# Mfd3.net
KiCad netlist of a schematic drawn in Altium Designer
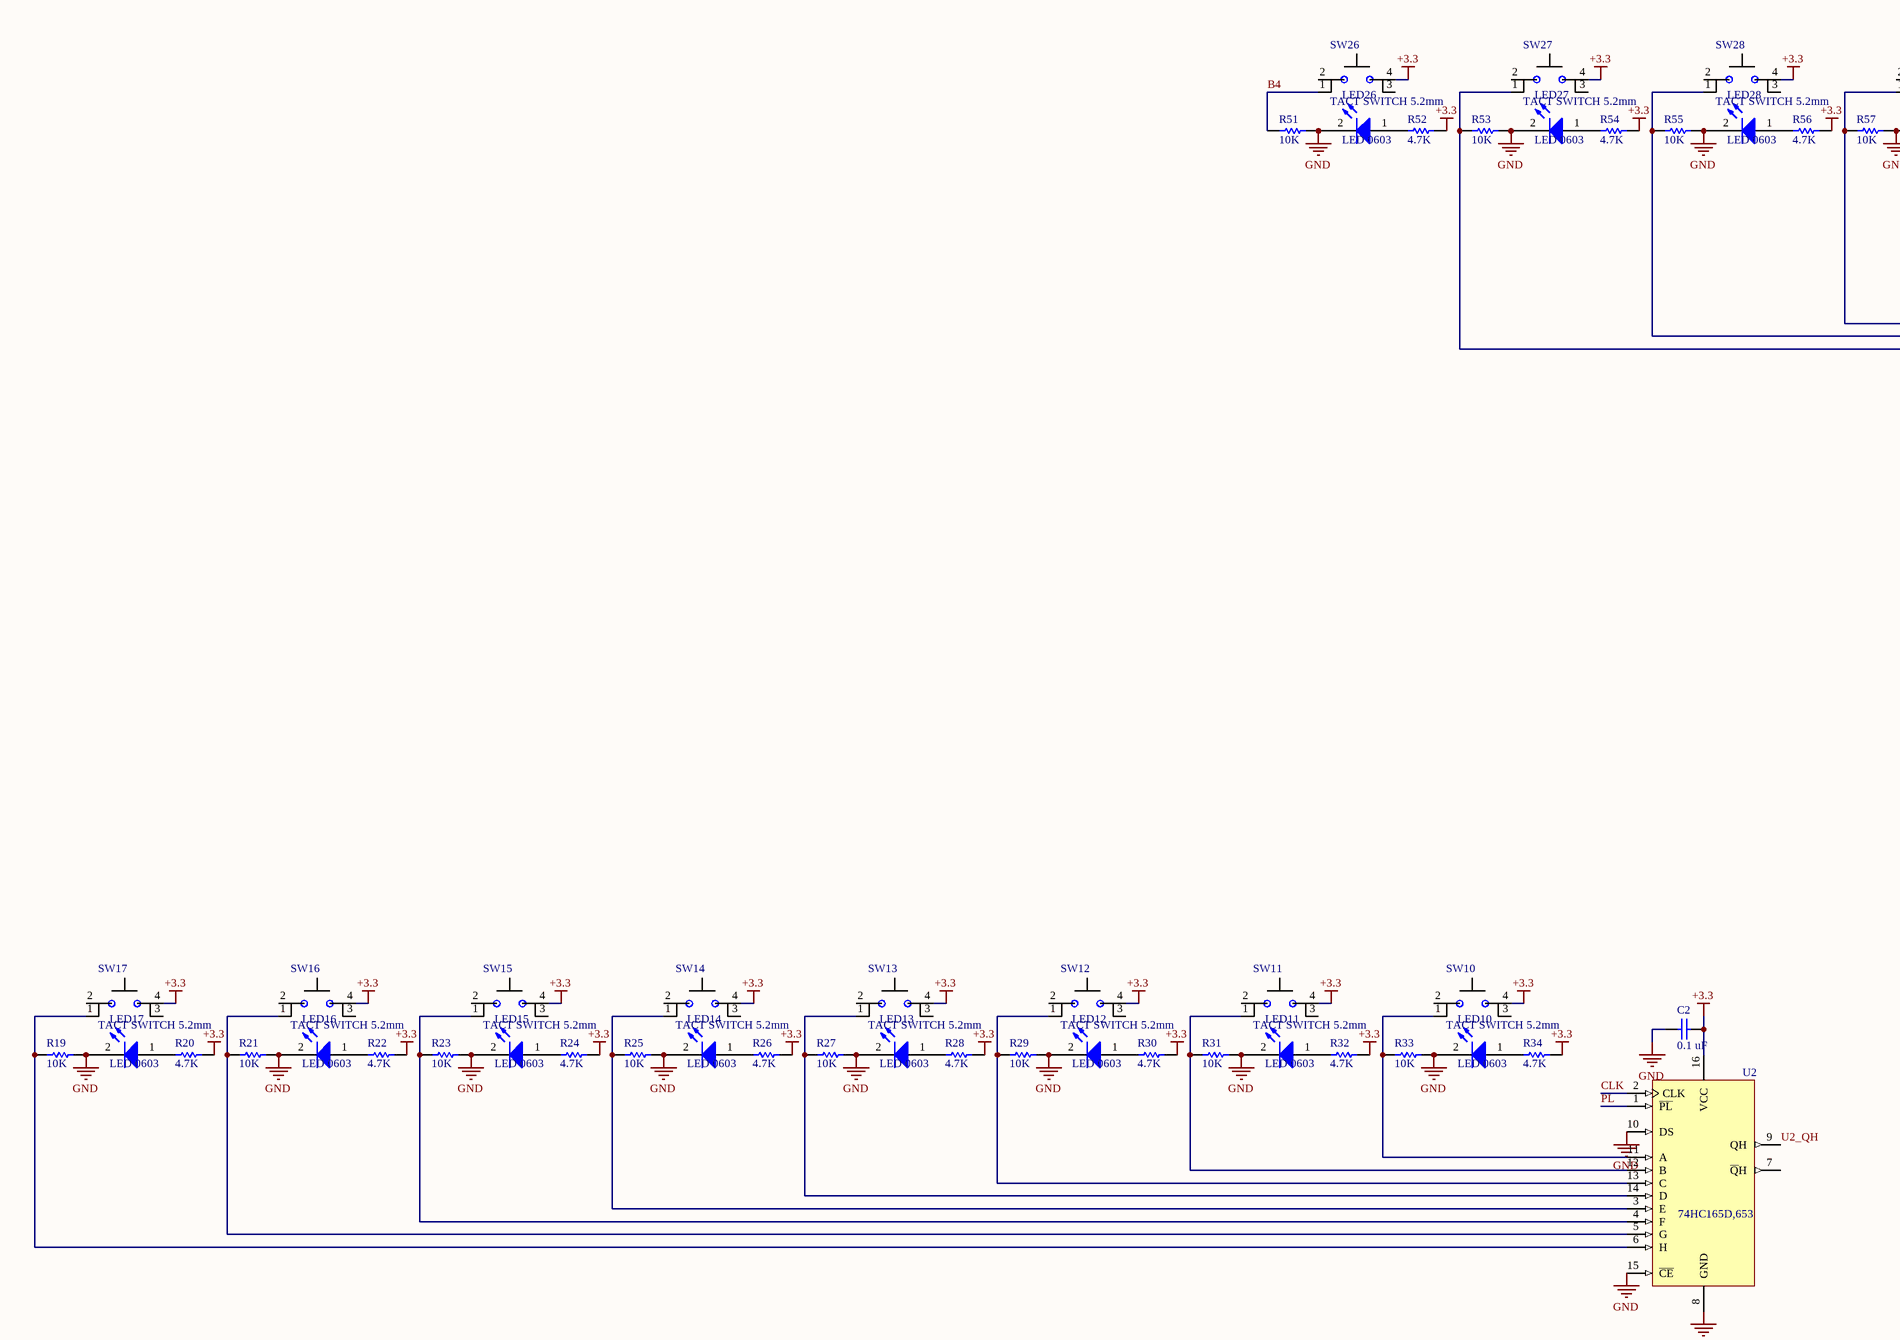
[diagram p0: Mfd3.SchDoc, top left]
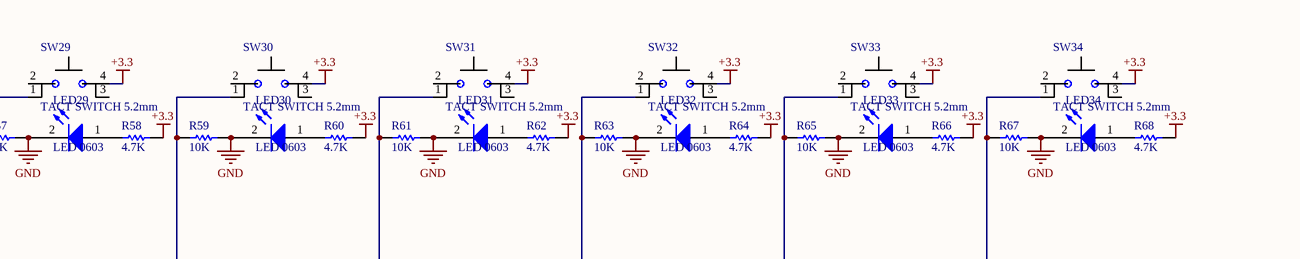
[diagram p1: Mfd3.SchDoc, top middle]
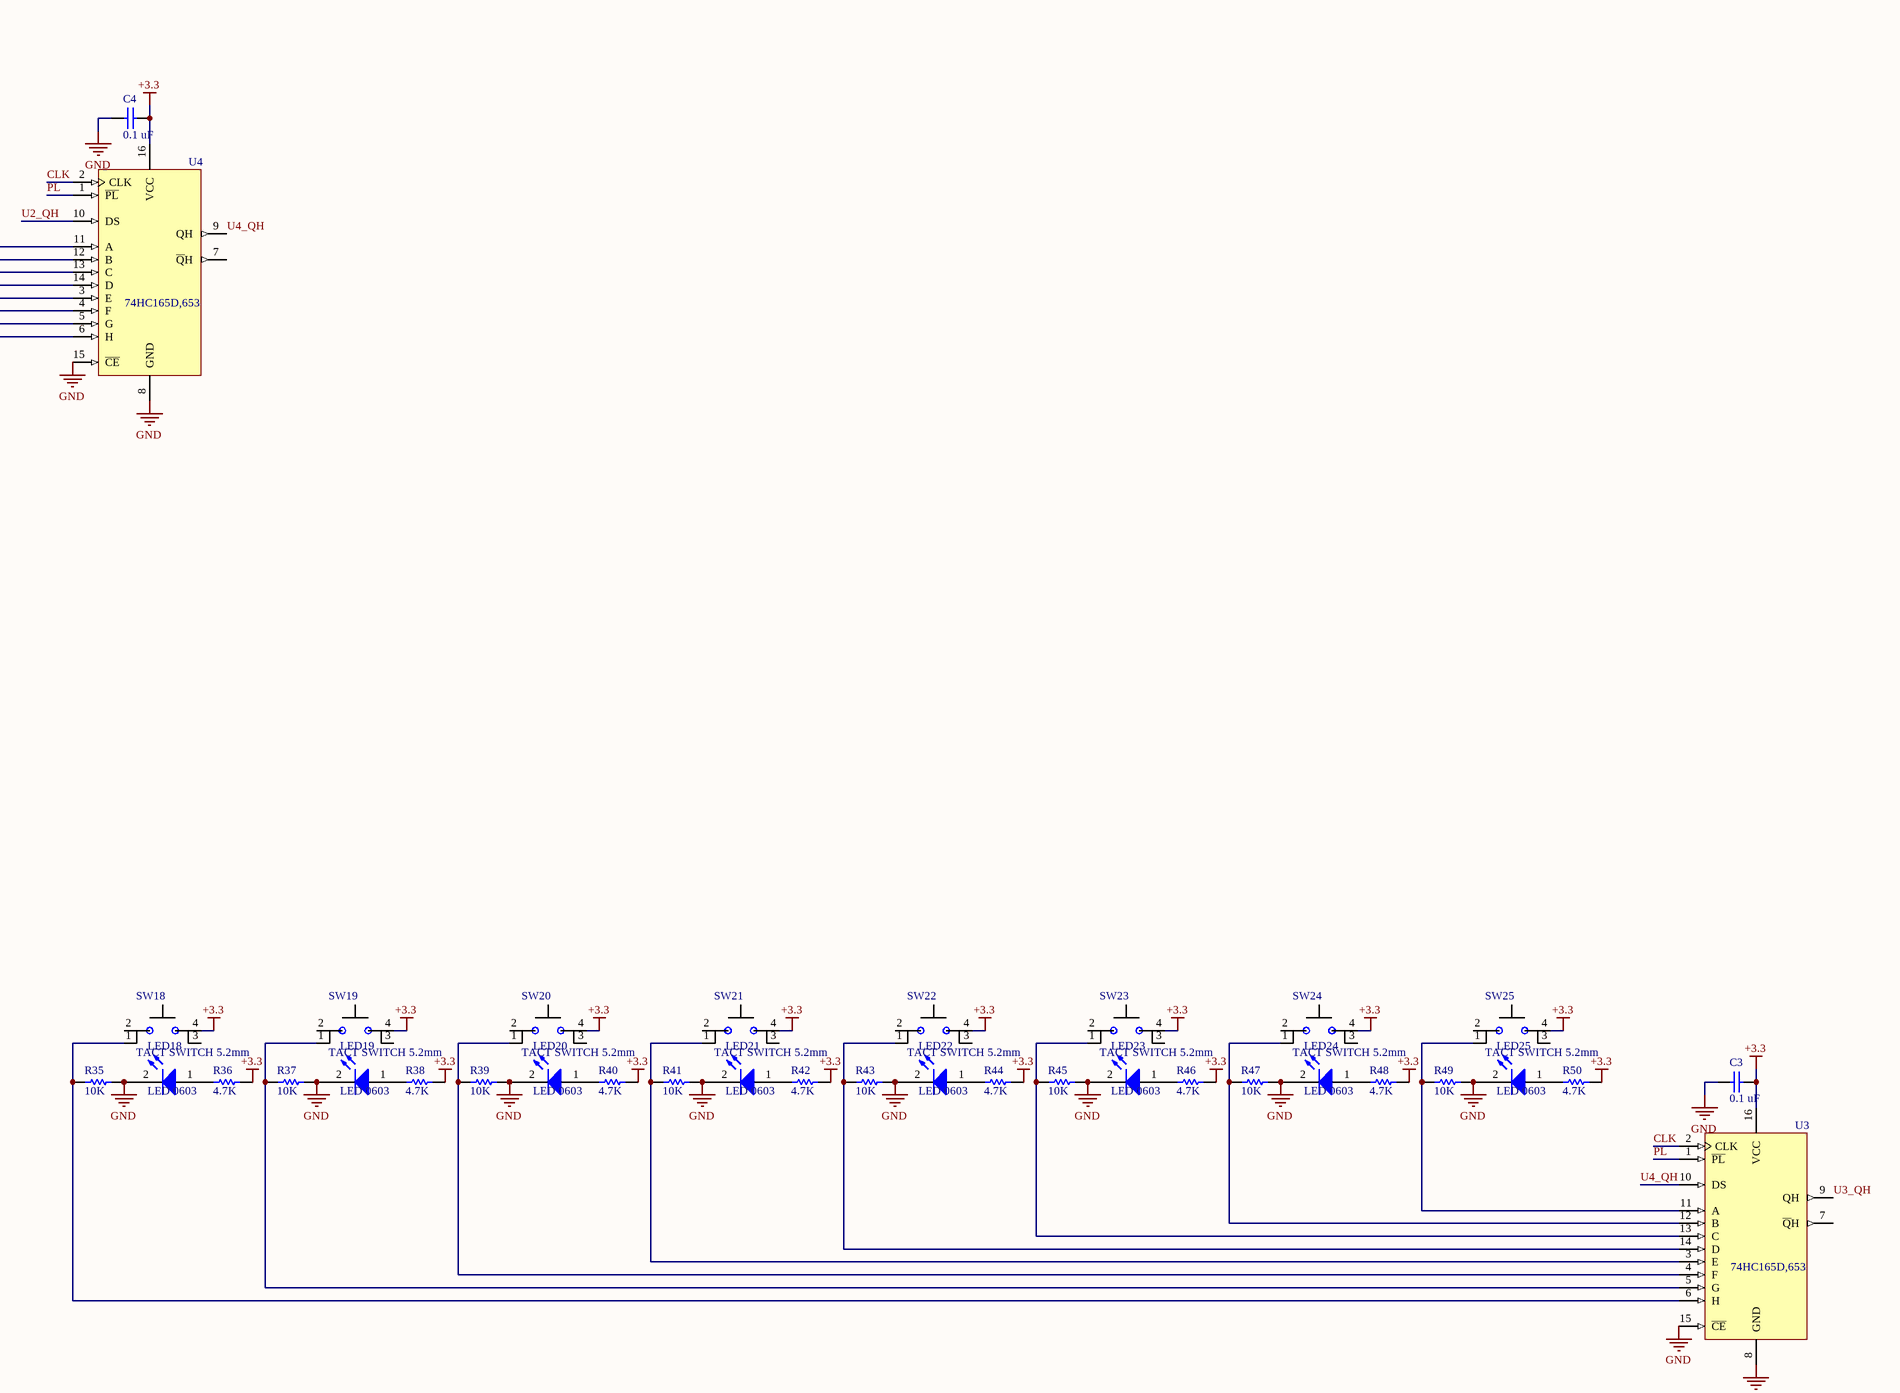
[diagram p2: Mfd3.SchDoc, top right]
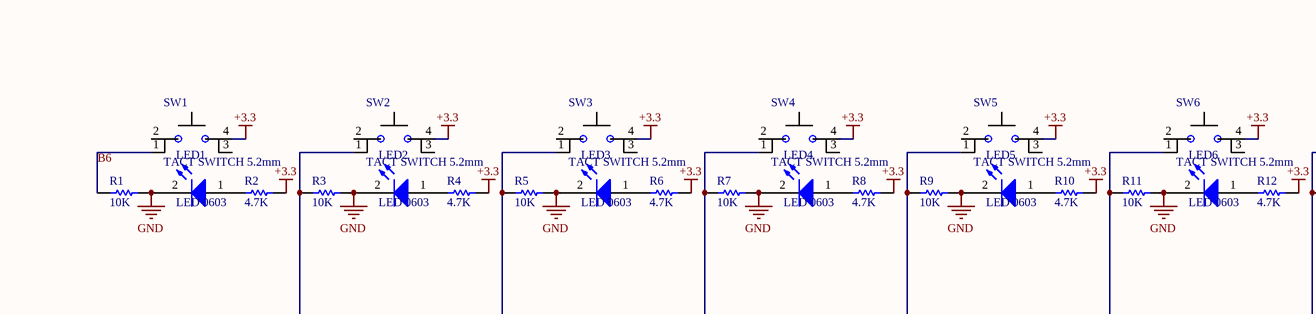
[diagram p3: Mfd3.SchDoc, bottom left]
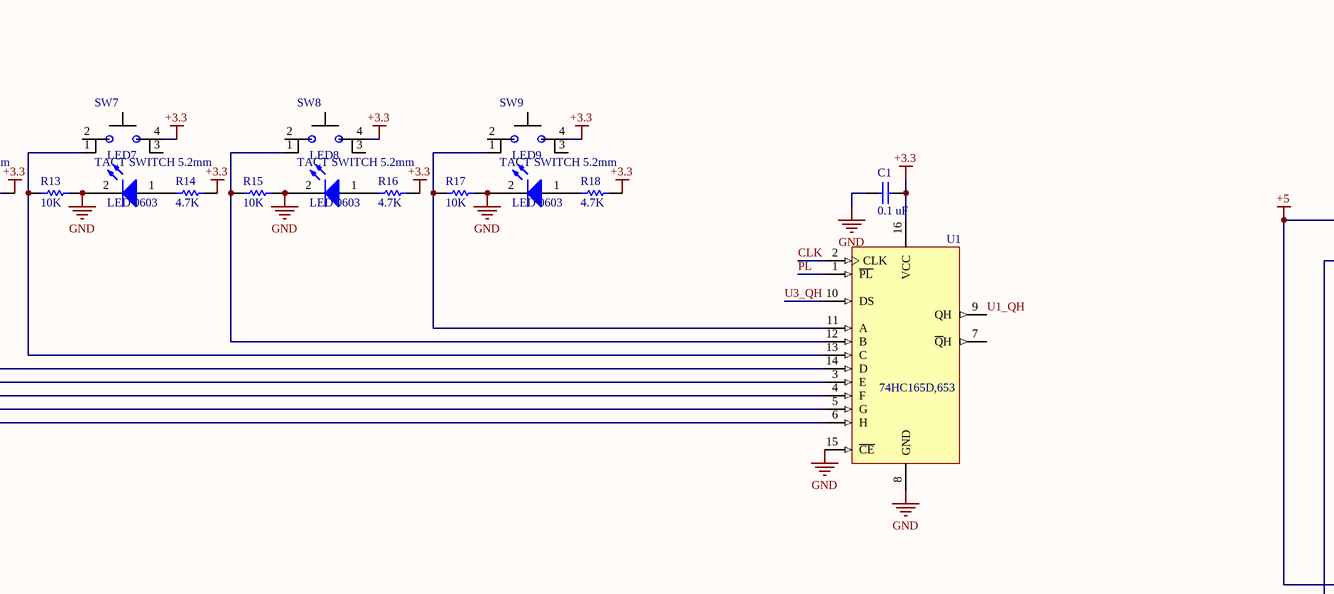
[diagram p4: Mfd3.SchDoc, bottom middle]
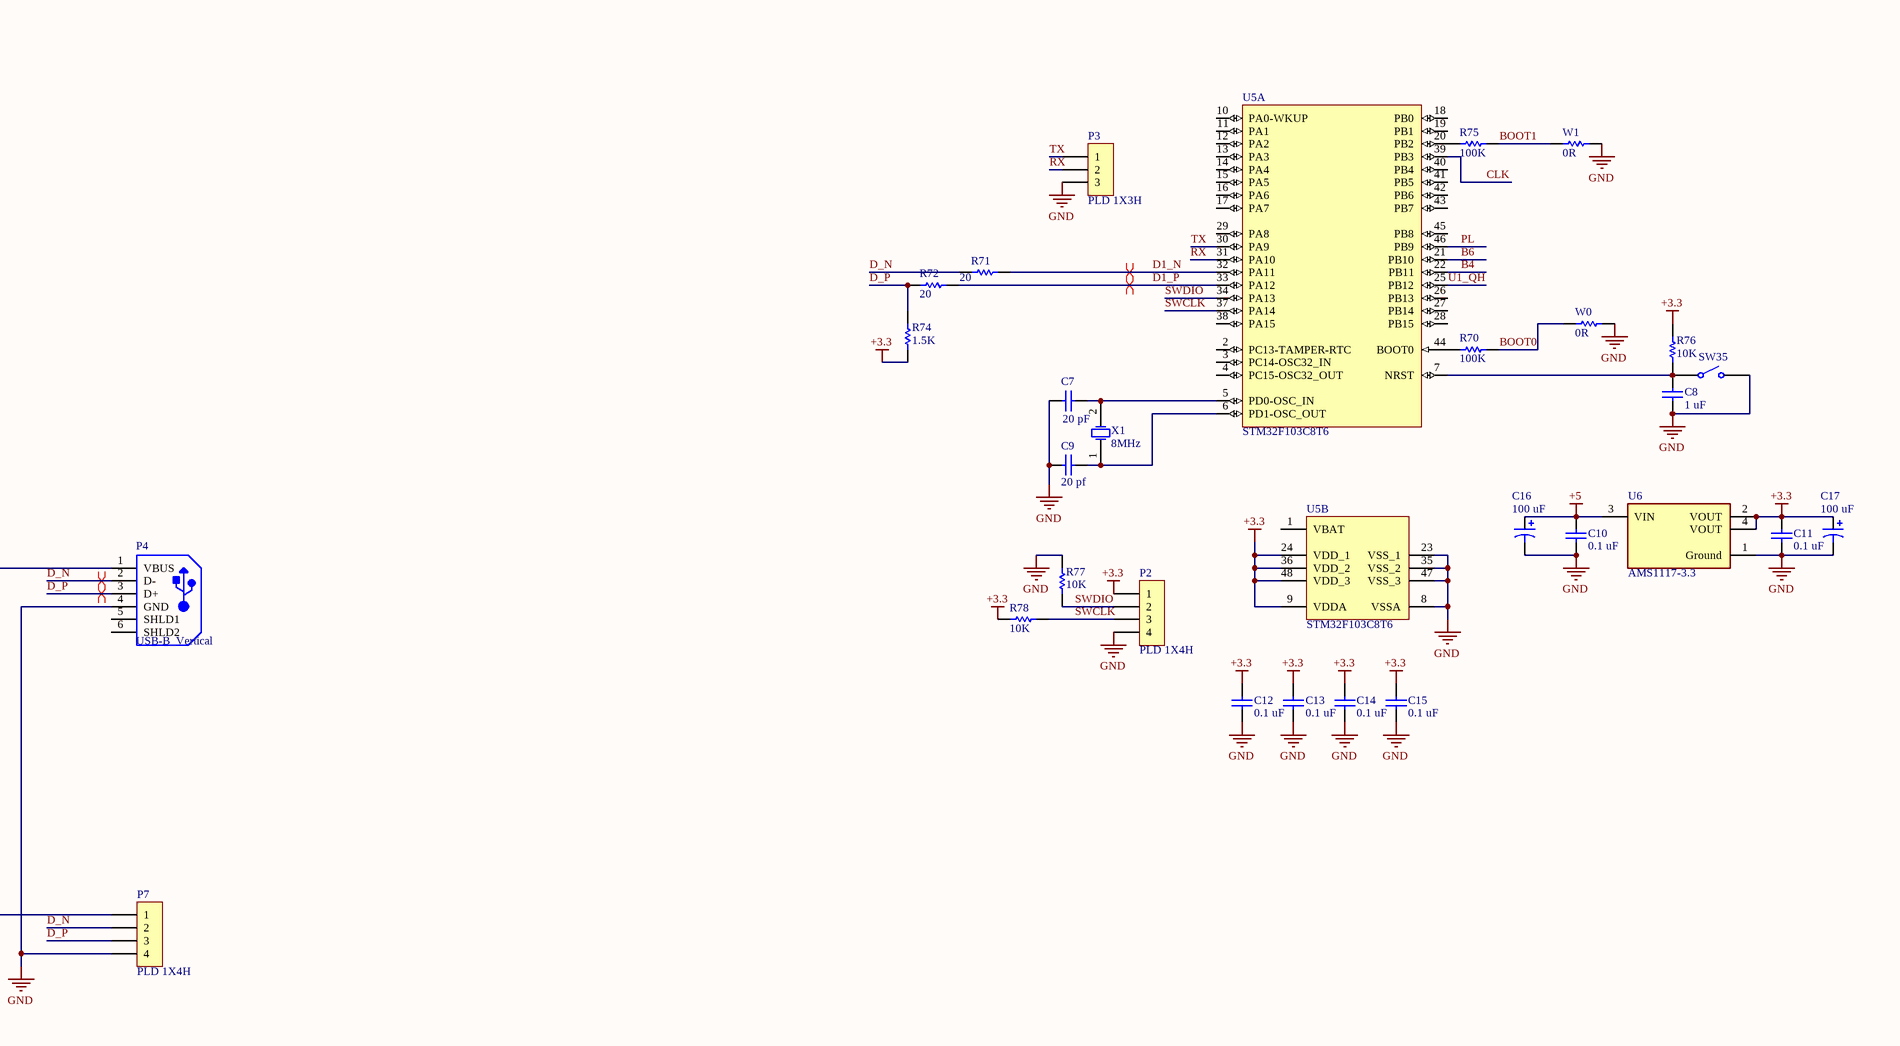
[diagram p5: Mfd3.SchDoc, bottom right]

(export (version "E")
  (design (tool "Eeschema 10.0.6"))
  (components
    (comp (ref "C1")
      (value "0.1 uF")
      (footprint "1206-CAP")
      (description "Chip Capacitor, 1206")
      (fields (field (name "LCSC PART #") "C24497"))
      (libsource (lib "Mfd3Schlib") (part "Capacitor"))
    )
    (comp (ref "C2")
      (value "0.1 uF")
      (footprint "1206-CAP")
      (description "Chip Capacitor, 1206")
      (fields (field (name "LCSC PART #") "C24497"))
      (libsource (lib "Mfd3Schlib") (part "Capacitor"))
    )
    (comp (ref "C3")
      (value "0.1 uF")
      (footprint "1206-CAP")
      (description "Chip Capacitor, 1206")
      (fields (field (name "LCSC PART #") "C24497"))
      (libsource (lib "Mfd3Schlib") (part "Capacitor"))
    )
    (comp (ref "C4")
      (value "0.1 uF")
      (footprint "1206-CAP")
      (description "Chip Capacitor, 1206")
      (fields (field (name "LCSC PART #") "C24497"))
      (libsource (lib "Mfd3Schlib") (part "Capacitor"))
    )
    (comp (ref "C7")
      (value "20 pF")
      (footprint "0805 CAP")
      (description "Chip Capacitor, 1206")
      (fields (field (name "LCSC PART #") "C1798"))
      (libsource (lib "Mfd3Schlib") (part "Capacitor"))
    )
    (comp (ref "C8")
      (value "1 uF")
      (footprint "1206-CAP")
      (description "Chip Capacitor, 1206")
      (fields (field (name "LCSC PART #") "C1848"))
      (libsource (lib "Mfd3Schlib") (part "Capacitor"))
    )
    (comp (ref "C9")
      (value "20 pf")
      (footprint "0805 CAP")
      (description "Chip Capacitor, 1206")
      (fields (field (name "LCSC PART #") "C1798"))
      (libsource (lib "Mfd3Schlib") (part "Capacitor"))
    )
    (comp (ref "C10")
      (value "0.1 uF")
      (footprint "1206-CAP")
      (description "Chip Capacitor, 1206")
      (fields (field (name "LCSC PART #") "C24497"))
      (libsource (lib "Mfd3Schlib") (part "Capacitor"))
    )
    (comp (ref "C11")
      (value "0.1 uF")
      (footprint "1206-CAP")
      (description "Chip Capacitor, 1206")
      (fields (field (name "LCSC PART #") "C24497"))
      (libsource (lib "Mfd3Schlib") (part "Capacitor"))
    )
    (comp (ref "C12")
      (value "0.1 uF")
      (footprint "1206-CAP")
      (description "Chip Capacitor, 1206")
      (fields (field (name "LCSC PART #") "C24497"))
      (libsource (lib "Mfd3Schlib") (part "Capacitor"))
    )
    (comp (ref "C13")
      (value "0.1 uF")
      (footprint "1206-CAP")
      (description "Chip Capacitor, 1206")
      (fields (field (name "LCSC PART #") "C24497"))
      (libsource (lib "Mfd3Schlib") (part "Capacitor"))
    )
    (comp (ref "C14")
      (value "0.1 uF")
      (footprint "1206-CAP")
      (description "Chip Capacitor, 1206")
      (fields (field (name "LCSC PART #") "C24497"))
      (libsource (lib "Mfd3Schlib") (part "Capacitor"))
    )
    (comp (ref "C15")
      (value "0.1 uF")
      (footprint "1206-CAP")
      (description "Chip Capacitor, 1206")
      (fields (field (name "LCSC PART #") "C24497"))
      (libsource (lib "Mfd3Schlib") (part "Capacitor"))
    )
    (comp (ref "C16")
      (value "100 uF")
      (footprint "1210 Cap")
      (description "Tantalum Capacitor, 1210")
      (fields (field (name "LCSC PART #") "C16133"))
      (libsource (lib "Mfd3Schlib") (part "Capacitor Tantalum"))
    )
    (comp (ref "C17")
      (value "100 uF")
      (footprint "1210 Cap")
      (description "Tantalum Capacitor, 1210")
      (fields (field (name "LCSC PART #") "C16133"))
      (libsource (lib "Mfd3Schlib") (part "Capacitor Tantalum"))
    )
    (comp (ref "LED1")
      (value "LED 0603")
      (footprint "LED 0603")
      (fields (field (name "LCSC PART #") "C72043"))
      (libsource (lib "Mfd3Schlib") (part "LED 0603"))
    )
    (comp (ref "LED2")
      (value "LED 0603")
      (footprint "LED 0603")
      (fields (field (name "LCSC PART #") "C72043"))
      (libsource (lib "Mfd3Schlib") (part "LED 0603"))
    )
    (comp (ref "LED3")
      (value "LED 0603")
      (footprint "LED 0603")
      (fields (field (name "LCSC PART #") "C72043"))
      (libsource (lib "Mfd3Schlib") (part "LED 0603"))
    )
    (comp (ref "LED4")
      (value "LED 0603")
      (footprint "LED 0603")
      (fields (field (name "LCSC PART #") "C72043"))
      (libsource (lib "Mfd3Schlib") (part "LED 0603"))
    )
    (comp (ref "LED5")
      (value "LED 0603")
      (footprint "LED 0603")
      (fields (field (name "LCSC PART #") "C72043"))
      (libsource (lib "Mfd3Schlib") (part "LED 0603"))
    )
    (comp (ref "LED6")
      (value "LED 0603")
      (footprint "LED 0603")
      (fields (field (name "LCSC PART #") "C72043"))
      (libsource (lib "Mfd3Schlib") (part "LED 0603"))
    )
    (comp (ref "LED7")
      (value "LED 0603")
      (footprint "LED 0603")
      (fields (field (name "LCSC PART #") "C72043"))
      (libsource (lib "Mfd3Schlib") (part "LED 0603"))
    )
    (comp (ref "LED8")
      (value "LED 0603")
      (footprint "LED 0603")
      (fields (field (name "LCSC PART #") "C72043"))
      (libsource (lib "Mfd3Schlib") (part "LED 0603"))
    )
    (comp (ref "LED9")
      (value "LED 0603")
      (footprint "LED 0603")
      (fields (field (name "LCSC PART #") "C72043"))
      (libsource (lib "Mfd3Schlib") (part "LED 0603"))
    )
    (comp (ref "LED10")
      (value "LED 0603")
      (footprint "LED 0603")
      (fields (field (name "LCSC PART #") "C72043"))
      (libsource (lib "Mfd3Schlib") (part "LED 0603"))
    )
    (comp (ref "LED11")
      (value "LED 0603")
      (footprint "LED 0603")
      (fields (field (name "LCSC PART #") "C72043"))
      (libsource (lib "Mfd3Schlib") (part "LED 0603"))
    )
    (comp (ref "LED12")
      (value "LED 0603")
      (footprint "LED 0603")
      (fields (field (name "LCSC PART #") "C72043"))
      (libsource (lib "Mfd3Schlib") (part "LED 0603"))
    )
    (comp (ref "LED13")
      (value "LED 0603")
      (footprint "LED 0603")
      (fields (field (name "LCSC PART #") "C72043"))
      (libsource (lib "Mfd3Schlib") (part "LED 0603"))
    )
    (comp (ref "LED14")
      (value "LED 0603")
      (footprint "LED 0603")
      (fields (field (name "LCSC PART #") "C72043"))
      (libsource (lib "Mfd3Schlib") (part "LED 0603"))
    )
    (comp (ref "LED15")
      (value "LED 0603")
      (footprint "LED 0603")
      (fields (field (name "LCSC PART #") "C72043"))
      (libsource (lib "Mfd3Schlib") (part "LED 0603"))
    )
    (comp (ref "LED16")
      (value "LED 0603")
      (footprint "LED 0603")
      (fields (field (name "LCSC PART #") "C72043"))
      (libsource (lib "Mfd3Schlib") (part "LED 0603"))
    )
    (comp (ref "LED17")
      (value "LED 0603")
      (footprint "LED 0603")
      (fields (field (name "LCSC PART #") "C72043"))
      (libsource (lib "Mfd3Schlib") (part "LED 0603"))
    )
    (comp (ref "LED18")
      (value "LED 0603")
      (footprint "LED 0603")
      (fields (field (name "LCSC PART #") "C72043"))
      (libsource (lib "Mfd3Schlib") (part "LED 0603"))
    )
    (comp (ref "LED19")
      (value "LED 0603")
      (footprint "LED 0603")
      (fields (field (name "LCSC PART #") "C72043"))
      (libsource (lib "Mfd3Schlib") (part "LED 0603"))
    )
    (comp (ref "LED20")
      (value "LED 0603")
      (footprint "LED 0603")
      (fields (field (name "LCSC PART #") "C72043"))
      (libsource (lib "Mfd3Schlib") (part "LED 0603"))
    )
    (comp (ref "LED21")
      (value "LED 0603")
      (footprint "LED 0603")
      (fields (field (name "LCSC PART #") "C72043"))
      (libsource (lib "Mfd3Schlib") (part "LED 0603"))
    )
    (comp (ref "LED22")
      (value "LED 0603")
      (footprint "LED 0603")
      (fields (field (name "LCSC PART #") "C72043"))
      (libsource (lib "Mfd3Schlib") (part "LED 0603"))
    )
    (comp (ref "LED23")
      (value "LED 0603")
      (footprint "LED 0603")
      (fields (field (name "LCSC PART #") "C72043"))
      (libsource (lib "Mfd3Schlib") (part "LED 0603"))
    )
    (comp (ref "LED24")
      (value "LED 0603")
      (footprint "LED 0603")
      (fields (field (name "LCSC PART #") "C72043"))
      (libsource (lib "Mfd3Schlib") (part "LED 0603"))
    )
    (comp (ref "LED25")
      (value "LED 0603")
      (footprint "LED 0603")
      (fields (field (name "LCSC PART #") "C72043"))
      (libsource (lib "Mfd3Schlib") (part "LED 0603"))
    )
    (comp (ref "LED26")
      (value "LED 0603")
      (footprint "LED 0603")
      (fields (field (name "LCSC PART #") "C72043"))
      (libsource (lib "Mfd3Schlib") (part "LED 0603"))
    )
    (comp (ref "LED27")
      (value "LED 0603")
      (footprint "LED 0603")
      (fields (field (name "LCSC PART #") "C72043"))
      (libsource (lib "Mfd3Schlib") (part "LED 0603"))
    )
    (comp (ref "LED28")
      (value "LED 0603")
      (footprint "LED 0603")
      (fields (field (name "LCSC PART #") "C72043"))
      (libsource (lib "Mfd3Schlib") (part "LED 0603"))
    )
    (comp (ref "LED29")
      (value "LED 0603")
      (footprint "LED 0603")
      (fields (field (name "LCSC PART #") "C72043"))
      (libsource (lib "Mfd3Schlib") (part "LED 0603"))
    )
    (comp (ref "LED30")
      (value "LED 0603")
      (footprint "LED 0603")
      (fields (field (name "LCSC PART #") "C72043"))
      (libsource (lib "Mfd3Schlib") (part "LED 0603"))
    )
    (comp (ref "LED31")
      (value "LED 0603")
      (footprint "LED 0603")
      (fields (field (name "LCSC PART #") "C72043"))
      (libsource (lib "Mfd3Schlib") (part "LED 0603"))
    )
    (comp (ref "LED32")
      (value "LED 0603")
      (footprint "LED 0603")
      (fields (field (name "LCSC PART #") "C72043"))
      (libsource (lib "Mfd3Schlib") (part "LED 0603"))
    )
    (comp (ref "LED33")
      (value "LED 0603")
      (footprint "LED 0603")
      (fields (field (name "LCSC PART #") "C72043"))
      (libsource (lib "Mfd3Schlib") (part "LED 0603"))
    )
    (comp (ref "LED34")
      (value "LED 0603")
      (footprint "LED 0603")
      (fields (field (name "LCSC PART #") "C72043"))
      (libsource (lib "Mfd3Schlib") (part "LED 0603"))
    )
    (comp (ref "P2")
      (value "PLD 1X4H")
      (footprint "PLD 1X4H")
      (description "Header, 4-Pin, SIngle row, Right Angle")
      (libsource (lib "MfdSchlib") (part "PLD 1X4H"))
    )
    (comp (ref "P3")
      (value "PLD 1X3H")
      (footprint "PLD 1X3H")
      (description "Header, 3-Pin, SIngle row, Right Angle")
      (libsource (lib "Mfd3Schlib") (part "PLD 1X3H"))
    )
    (comp (ref "P4")
      (value "USB-B_Vertical")
      (footprint "USB-B_Vertical")
      (libsource (lib "MfdSchlib") (part "USB-B_Vertical"))
    )
    (comp (ref "P7")
      (value "PLD 1X4H")
      (footprint "PLD 1X4H")
      (description "Header, 4-Pin, SIngle row, Right Angle")
      (libsource (lib "MfdSchlib") (part "PLD 1X4H"))
    )
    (comp (ref "R1")
      (value "10K")
      (footprint "1206")
      (description "Resistor 1206")
      (fields (field (name "LCSC PART #") "C17902"))
      (libsource (lib "MfdSchlib") (part "Resistor"))
    )
    (comp (ref "R2")
      (value "4.7K")
      (footprint "1206")
      (description "Resistor 1206")
      (fields (field (name "LCSC PART #") "C17936"))
      (libsource (lib "MfdSchlib") (part "Resistor"))
    )
    (comp (ref "R3")
      (value "10K")
      (footprint "1206")
      (description "Resistor 1206")
      (fields (field (name "LCSC PART #") "C17902"))
      (libsource (lib "MfdSchlib") (part "Resistor"))
    )
    (comp (ref "R4")
      (value "4.7K")
      (footprint "1206")
      (description "Resistor 1206")
      (fields (field (name "LCSC PART #") "C17936"))
      (libsource (lib "MfdSchlib") (part "Resistor"))
    )
    (comp (ref "R5")
      (value "10K")
      (footprint "1206")
      (description "Resistor 1206")
      (fields (field (name "LCSC PART #") "C17902"))
      (libsource (lib "MfdSchlib") (part "Resistor"))
    )
    (comp (ref "R6")
      (value "4.7K")
      (footprint "1206")
      (description "Resistor 1206")
      (fields (field (name "LCSC PART #") "C17936"))
      (libsource (lib "MfdSchlib") (part "Resistor"))
    )
    (comp (ref "R7")
      (value "10K")
      (footprint "1206")
      (description "Resistor 1206")
      (fields (field (name "LCSC PART #") "C17902"))
      (libsource (lib "MfdSchlib") (part "Resistor"))
    )
    (comp (ref "R8")
      (value "4.7K")
      (footprint "1206")
      (description "Resistor 1206")
      (fields (field (name "LCSC PART #") "C17936"))
      (libsource (lib "MfdSchlib") (part "Resistor"))
    )
    (comp (ref "R9")
      (value "10K")
      (footprint "1206")
      (description "Resistor 1206")
      (fields (field (name "LCSC PART #") "C17902"))
      (libsource (lib "MfdSchlib") (part "Resistor"))
    )
    (comp (ref "R10")
      (value "4.7K")
      (footprint "1206")
      (description "Resistor 1206")
      (fields (field (name "LCSC PART #") "C17936"))
      (libsource (lib "MfdSchlib") (part "Resistor"))
    )
    (comp (ref "R11")
      (value "10K")
      (footprint "1206")
      (description "Resistor 1206")
      (fields (field (name "LCSC PART #") "C17902"))
      (libsource (lib "MfdSchlib") (part "Resistor"))
    )
    (comp (ref "R12")
      (value "4.7K")
      (footprint "1206")
      (description "Resistor 1206")
      (fields (field (name "LCSC PART #") "C17936"))
      (libsource (lib "MfdSchlib") (part "Resistor"))
    )
    (comp (ref "R13")
      (value "10K")
      (footprint "1206")
      (description "Resistor 1206")
      (fields (field (name "LCSC PART #") "C17902"))
      (libsource (lib "MfdSchlib") (part "Resistor"))
    )
    (comp (ref "R14")
      (value "4.7K")
      (footprint "1206")
      (description "Resistor 1206")
      (fields (field (name "LCSC PART #") "C17936"))
      (libsource (lib "MfdSchlib") (part "Resistor"))
    )
    (comp (ref "R15")
      (value "10K")
      (footprint "1206")
      (description "Resistor 1206")
      (fields (field (name "LCSC PART #") "C17902"))
      (libsource (lib "MfdSchlib") (part "Resistor"))
    )
    (comp (ref "R16")
      (value "4.7K")
      (footprint "1206")
      (description "Resistor 1206")
      (fields (field (name "LCSC PART #") "C17936"))
      (libsource (lib "MfdSchlib") (part "Resistor"))
    )
    (comp (ref "R17")
      (value "10K")
      (footprint "1206")
      (description "Resistor 1206")
      (fields (field (name "LCSC PART #") "C17902"))
      (libsource (lib "MfdSchlib") (part "Resistor"))
    )
    (comp (ref "R18")
      (value "4.7K")
      (footprint "1206")
      (description "Resistor 1206")
      (fields (field (name "LCSC PART #") "C17936"))
      (libsource (lib "MfdSchlib") (part "Resistor"))
    )
    (comp (ref "R19")
      (value "10K")
      (footprint "1206")
      (description "Resistor 1206")
      (fields (field (name "LCSC PART #") "C17902"))
      (libsource (lib "MfdSchlib") (part "Resistor"))
    )
    (comp (ref "R20")
      (value "4.7K")
      (footprint "1206")
      (description "Resistor 1206")
      (fields (field (name "LCSC PART #") "C17936"))
      (libsource (lib "MfdSchlib") (part "Resistor"))
    )
    (comp (ref "R21")
      (value "10K")
      (footprint "1206")
      (description "Resistor 1206")
      (fields (field (name "LCSC PART #") "C17902"))
      (libsource (lib "MfdSchlib") (part "Resistor"))
    )
    (comp (ref "R22")
      (value "4.7K")
      (footprint "1206")
      (description "Resistor 1206")
      (fields (field (name "LCSC PART #") "C17936"))
      (libsource (lib "MfdSchlib") (part "Resistor"))
    )
    (comp (ref "R23")
      (value "10K")
      (footprint "1206")
      (description "Resistor 1206")
      (fields (field (name "LCSC PART #") "C17902"))
      (libsource (lib "MfdSchlib") (part "Resistor"))
    )
    (comp (ref "R24")
      (value "4.7K")
      (footprint "1206")
      (description "Resistor 1206")
      (fields (field (name "LCSC PART #") "C17936"))
      (libsource (lib "MfdSchlib") (part "Resistor"))
    )
    (comp (ref "R25")
      (value "10K")
      (footprint "1206")
      (description "Resistor 1206")
      (fields (field (name "LCSC PART #") "C17902"))
      (libsource (lib "MfdSchlib") (part "Resistor"))
    )
    (comp (ref "R26")
      (value "4.7K")
      (footprint "1206")
      (description "Resistor 1206")
      (fields (field (name "LCSC PART #") "C17936"))
      (libsource (lib "MfdSchlib") (part "Resistor"))
    )
    (comp (ref "R27")
      (value "10K")
      (footprint "1206")
      (description "Resistor 1206")
      (fields (field (name "LCSC PART #") "C17902"))
      (libsource (lib "MfdSchlib") (part "Resistor"))
    )
    (comp (ref "R28")
      (value "4.7K")
      (footprint "1206")
      (description "Resistor 1206")
      (fields (field (name "LCSC PART #") "C17936"))
      (libsource (lib "MfdSchlib") (part "Resistor"))
    )
    (comp (ref "R29")
      (value "10K")
      (footprint "1206")
      (description "Resistor 1206")
      (fields (field (name "LCSC PART #") "C17902"))
      (libsource (lib "MfdSchlib") (part "Resistor"))
    )
    (comp (ref "R30")
      (value "4.7K")
      (footprint "1206")
      (description "Resistor 1206")
      (fields (field (name "LCSC PART #") "C17936"))
      (libsource (lib "MfdSchlib") (part "Resistor"))
    )
    (comp (ref "R31")
      (value "10K")
      (footprint "1206")
      (description "Resistor 1206")
      (fields (field (name "LCSC PART #") "C17902"))
      (libsource (lib "MfdSchlib") (part "Resistor"))
    )
    (comp (ref "R32")
      (value "4.7K")
      (footprint "1206")
      (description "Resistor 1206")
      (fields (field (name "LCSC PART #") "C17936"))
      (libsource (lib "MfdSchlib") (part "Resistor"))
    )
    (comp (ref "R33")
      (value "10K")
      (footprint "1206")
      (description "Resistor 1206")
      (fields (field (name "LCSC PART #") "C17902"))
      (libsource (lib "MfdSchlib") (part "Resistor"))
    )
    (comp (ref "R34")
      (value "4.7K")
      (footprint "1206")
      (description "Resistor 1206")
      (fields (field (name "LCSC PART #") "C17936"))
      (libsource (lib "MfdSchlib") (part "Resistor"))
    )
    (comp (ref "R35")
      (value "10K")
      (footprint "1206")
      (description "Resistor 1206")
      (fields (field (name "LCSC PART #") "C17902"))
      (libsource (lib "MfdSchlib") (part "Resistor"))
    )
    (comp (ref "R36")
      (value "4.7K")
      (footprint "1206")
      (description "Resistor 1206")
      (fields (field (name "LCSC PART #") "C17936"))
      (libsource (lib "MfdSchlib") (part "Resistor"))
    )
    (comp (ref "R37")
      (value "10K")
      (footprint "1206")
      (description "Resistor 1206")
      (fields (field (name "LCSC PART #") "C17902"))
      (libsource (lib "MfdSchlib") (part "Resistor"))
    )
    (comp (ref "R38")
      (value "4.7K")
      (footprint "1206")
      (description "Resistor 1206")
      (fields (field (name "LCSC PART #") "C17936"))
      (libsource (lib "MfdSchlib") (part "Resistor"))
    )
    (comp (ref "R39")
      (value "10K")
      (footprint "1206")
      (description "Resistor 1206")
      (fields (field (name "LCSC PART #") "C17902"))
      (libsource (lib "MfdSchlib") (part "Resistor"))
    )
    (comp (ref "R40")
      (value "4.7K")
      (footprint "1206")
      (description "Resistor 1206")
      (fields (field (name "LCSC PART #") "C17936"))
      (libsource (lib "MfdSchlib") (part "Resistor"))
    )
    (comp (ref "R41")
      (value "10K")
      (footprint "1206")
      (description "Resistor 1206")
      (fields (field (name "LCSC PART #") "C17902"))
      (libsource (lib "MfdSchlib") (part "Resistor"))
    )
    (comp (ref "R42")
      (value "4.7K")
      (footprint "1206")
      (description "Resistor 1206")
      (fields (field (name "LCSC PART #") "C17936"))
      (libsource (lib "MfdSchlib") (part "Resistor"))
    )
    (comp (ref "R43")
      (value "10K")
      (footprint "1206")
      (description "Resistor 1206")
      (fields (field (name "LCSC PART #") "C17902"))
      (libsource (lib "MfdSchlib") (part "Resistor"))
    )
    (comp (ref "R44")
      (value "4.7K")
      (footprint "1206")
      (description "Resistor 1206")
      (fields (field (name "LCSC PART #") "C17936"))
      (libsource (lib "MfdSchlib") (part "Resistor"))
    )
    (comp (ref "R45")
      (value "10K")
      (footprint "1206")
      (description "Resistor 1206")
      (fields (field (name "LCSC PART #") "C17902"))
      (libsource (lib "MfdSchlib") (part "Resistor"))
    )
    (comp (ref "R46")
      (value "4.7K")
      (footprint "1206")
      (description "Resistor 1206")
      (fields (field (name "LCSC PART #") "C17936"))
      (libsource (lib "MfdSchlib") (part "Resistor"))
    )
    (comp (ref "R47")
      (value "10K")
      (footprint "1206")
      (description "Resistor 1206")
      (fields (field (name "LCSC PART #") "C17902"))
      (libsource (lib "MfdSchlib") (part "Resistor"))
    )
    (comp (ref "R48")
      (value "4.7K")
      (footprint "1206")
      (description "Resistor 1206")
      (fields (field (name "LCSC PART #") "C17936"))
      (libsource (lib "MfdSchlib") (part "Resistor"))
    )
    (comp (ref "R49")
      (value "10K")
      (footprint "1206")
      (description "Resistor 1206")
      (fields (field (name "LCSC PART #") "C17902"))
      (libsource (lib "MfdSchlib") (part "Resistor"))
    )
    (comp (ref "R50")
      (value "4.7K")
      (footprint "1206")
      (description "Resistor 1206")
      (fields (field (name "LCSC PART #") "C17936"))
      (libsource (lib "MfdSchlib") (part "Resistor"))
    )
    (comp (ref "R51")
      (value "10K")
      (footprint "1206")
      (description "Resistor 1206")
      (fields (field (name "LCSC PART #") "C17902"))
      (libsource (lib "MfdSchlib") (part "Resistor"))
    )
    (comp (ref "R52")
      (value "4.7K")
      (footprint "1206")
      (description "Resistor 1206")
      (fields (field (name "LCSC PART #") "C17936"))
      (libsource (lib "MfdSchlib") (part "Resistor"))
    )
    (comp (ref "R53")
      (value "10K")
      (footprint "1206")
      (description "Resistor 1206")
      (fields (field (name "LCSC PART #") "C17902"))
      (libsource (lib "MfdSchlib") (part "Resistor"))
    )
    (comp (ref "R54")
      (value "4.7K")
      (footprint "1206")
      (description "Resistor 1206")
      (fields (field (name "LCSC PART #") "C17936"))
      (libsource (lib "MfdSchlib") (part "Resistor"))
    )
    (comp (ref "R55")
      (value "10K")
      (footprint "1206")
      (description "Resistor 1206")
      (fields (field (name "LCSC PART #") "C17902"))
      (libsource (lib "MfdSchlib") (part "Resistor"))
    )
    (comp (ref "R56")
      (value "4.7K")
      (footprint "1206")
      (description "Resistor 1206")
      (fields (field (name "LCSC PART #") "C17936"))
      (libsource (lib "MfdSchlib") (part "Resistor"))
    )
    (comp (ref "R57")
      (value "10K")
      (footprint "1206")
      (description "Resistor 1206")
      (fields (field (name "LCSC PART #") "C17902"))
      (libsource (lib "MfdSchlib") (part "Resistor"))
    )
    (comp (ref "R58")
      (value "4.7K")
      (footprint "1206")
      (description "Resistor 1206")
      (fields (field (name "LCSC PART #") "C17936"))
      (libsource (lib "MfdSchlib") (part "Resistor"))
    )
    (comp (ref "R59")
      (value "10K")
      (footprint "1206")
      (description "Resistor 1206")
      (fields (field (name "LCSC PART #") "C17902"))
      (libsource (lib "MfdSchlib") (part "Resistor"))
    )
    (comp (ref "R60")
      (value "4.7K")
      (footprint "1206")
      (description "Resistor 1206")
      (fields (field (name "LCSC PART #") "C17936"))
      (libsource (lib "MfdSchlib") (part "Resistor"))
    )
    (comp (ref "R61")
      (value "10K")
      (footprint "1206")
      (description "Resistor 1206")
      (fields (field (name "LCSC PART #") "C17902"))
      (libsource (lib "MfdSchlib") (part "Resistor"))
    )
    (comp (ref "R62")
      (value "4.7K")
      (footprint "1206")
      (description "Resistor 1206")
      (fields (field (name "LCSC PART #") "C17936"))
      (libsource (lib "MfdSchlib") (part "Resistor"))
    )
    (comp (ref "R63")
      (value "10K")
      (footprint "1206")
      (description "Resistor 1206")
      (fields (field (name "LCSC PART #") "C17902"))
      (libsource (lib "MfdSchlib") (part "Resistor"))
    )
    (comp (ref "R64")
      (value "4.7K")
      (footprint "1206")
      (description "Resistor 1206")
      (fields (field (name "LCSC PART #") "C17936"))
      (libsource (lib "MfdSchlib") (part "Resistor"))
    )
    (comp (ref "R65")
      (value "10K")
      (footprint "1206")
      (description "Resistor 1206")
      (fields (field (name "LCSC PART #") "C17902"))
      (libsource (lib "MfdSchlib") (part "Resistor"))
    )
    (comp (ref "R66")
      (value "4.7K")
      (footprint "1206")
      (description "Resistor 1206")
      (fields (field (name "LCSC PART #") "C17936"))
      (libsource (lib "MfdSchlib") (part "Resistor"))
    )
    (comp (ref "R67")
      (value "10K")
      (footprint "1206")
      (description "Resistor 1206")
      (fields (field (name "LCSC PART #") "C17902"))
      (libsource (lib "MfdSchlib") (part "Resistor"))
    )
    (comp (ref "R68")
      (value "4.7K")
      (footprint "1206")
      (description "Resistor 1206")
      (fields (field (name "LCSC PART #") "C17936"))
      (libsource (lib "MfdSchlib") (part "Resistor"))
    )
    (comp (ref "R70")
      (value "100K")
      (footprint "1206")
      (description "Resistor 1206")
      (fields (field (name "LCSC PART #") "C17900"))
      (libsource (lib "MfdSchlib") (part "Resistor"))
    )
    (comp (ref "R71")
      (value "20")
      (footprint "1206")
      (description "Resistor 1206")
      (fields (field (name "LCSC PART #") "C17955"))
      (libsource (lib "MfdSchlib") (part "Resistor"))
    )
    (comp (ref "R72")
      (value "20")
      (footprint "1206")
      (description "Resistor 1206")
      (fields (field (name "LCSC PART #") "C17955"))
      (libsource (lib "MfdSchlib") (part "Resistor"))
    )
    (comp (ref "R74")
      (value "1.5K")
      (footprint "0805 RES")
      (description "Resistor 0805")
      (fields (field (name "LCSC PART #") "C4310"))
      (libsource (lib "Mfd3Schlib") (part "Resistor1"))
    )
    (comp (ref "R75")
      (value "100K")
      (footprint "1206")
      (description "Resistor 1206")
      (fields (field (name "LCSC PART #") "C17900"))
      (libsource (lib "MfdSchlib") (part "Resistor"))
    )
    (comp (ref "R76")
      (value "10K")
      (footprint "1206")
      (description "Resistor 1206")
      (fields (field (name "LCSC PART #") "C17902"))
      (libsource (lib "MfdSchlib") (part "Resistor"))
    )
    (comp (ref "R77")
      (value "10K")
      (footprint "1206")
      (description "Resistor 1206")
      (fields (field (name "LCSC PART #") "C17902"))
      (libsource (lib "MfdSchlib") (part "Resistor"))
    )
    (comp (ref "R78")
      (value "10K")
      (footprint "1206")
      (description "Resistor 1206")
      (fields (field (name "LCSC PART #") "C17902"))
      (libsource (lib "MfdSchlib") (part "Resistor"))
    )
    (comp (ref "SW1")
      (value "TACT SWITCH 5.2mm")
      (footprint "TACT SWITCH 5.2mm")
      (description "Push button 5.2 mm")
      (fields (field (name "LCSC PART #") "C412369"))
      (libsource (lib "Mfd3Schlib") (part "TACT SWITCH 5.2mm"))
    )
    (comp (ref "SW2")
      (value "TACT SWITCH 5.2mm")
      (footprint "TACT SWITCH 5.2mm")
      (description "Push button 5.2 mm")
      (fields (field (name "LCSC PART #") "C412369"))
      (libsource (lib "Mfd3Schlib") (part "TACT SWITCH 5.2mm"))
    )
    (comp (ref "SW3")
      (value "TACT SWITCH 5.2mm")
      (footprint "TACT SWITCH 5.2mm")
      (description "Push button 5.2 mm")
      (fields (field (name "LCSC PART #") "C412369"))
      (libsource (lib "Mfd3Schlib") (part "TACT SWITCH 5.2mm"))
    )
    (comp (ref "SW4")
      (value "TACT SWITCH 5.2mm")
      (footprint "TACT SWITCH 5.2mm")
      (description "Push button 5.2 mm")
      (fields (field (name "LCSC PART #") "C412369"))
      (libsource (lib "Mfd3Schlib") (part "TACT SWITCH 5.2mm"))
    )
    (comp (ref "SW5")
      (value "TACT SWITCH 5.2mm")
      (footprint "TACT SWITCH 5.2mm")
      (description "Push button 5.2 mm")
      (fields (field (name "LCSC PART #") "C412369"))
      (libsource (lib "Mfd3Schlib") (part "TACT SWITCH 5.2mm"))
    )
    (comp (ref "SW6")
      (value "TACT SWITCH 5.2mm")
      (footprint "TACT SWITCH 5.2mm")
      (description "Push button 5.2 mm")
      (fields (field (name "LCSC PART #") "C412369"))
      (libsource (lib "Mfd3Schlib") (part "TACT SWITCH 5.2mm"))
    )
    (comp (ref "SW7")
      (value "TACT SWITCH 5.2mm")
      (footprint "TACT SWITCH 5.2mm")
      (description "Push button 5.2 mm")
      (fields (field (name "LCSC PART #") "C412369"))
      (libsource (lib "Mfd3Schlib") (part "TACT SWITCH 5.2mm"))
    )
    (comp (ref "SW8")
      (value "TACT SWITCH 5.2mm")
      (footprint "TACT SWITCH 5.2mm")
      (description "Push button 5.2 mm")
      (fields (field (name "LCSC PART #") "C412369"))
      (libsource (lib "Mfd3Schlib") (part "TACT SWITCH 5.2mm"))
    )
    (comp (ref "SW9")
      (value "TACT SWITCH 5.2mm")
      (footprint "TACT SWITCH 5.2mm")
      (description "Push button 5.2 mm")
      (fields (field (name "LCSC PART #") "C412369"))
      (libsource (lib "Mfd3Schlib") (part "TACT SWITCH 5.2mm"))
    )
    (comp (ref "SW10")
      (value "TACT SWITCH 5.2mm")
      (footprint "TACT SWITCH 5.2mm")
      (description "Push button 5.2 mm")
      (fields (field (name "LCSC PART #") "C412369"))
      (libsource (lib "Mfd3Schlib") (part "TACT SWITCH 5.2mm"))
    )
    (comp (ref "SW11")
      (value "TACT SWITCH 5.2mm")
      (footprint "TACT SWITCH 5.2mm")
      (description "Push button 5.2 mm")
      (fields (field (name "LCSC PART #") "C412369"))
      (libsource (lib "Mfd3Schlib") (part "TACT SWITCH 5.2mm"))
    )
    (comp (ref "SW12")
      (value "TACT SWITCH 5.2mm")
      (footprint "TACT SWITCH 5.2mm")
      (description "Push button 5.2 mm")
      (fields (field (name "LCSC PART #") "C412369"))
      (libsource (lib "Mfd3Schlib") (part "TACT SWITCH 5.2mm"))
    )
    (comp (ref "SW13")
      (value "TACT SWITCH 5.2mm")
      (footprint "TACT SWITCH 5.2mm")
      (description "Push button 5.2 mm")
      (fields (field (name "LCSC PART #") "C412369"))
      (libsource (lib "Mfd3Schlib") (part "TACT SWITCH 5.2mm"))
    )
    (comp (ref "SW14")
      (value "TACT SWITCH 5.2mm")
      (footprint "TACT SWITCH 5.2mm")
      (description "Push button 5.2 mm")
      (fields (field (name "LCSC PART #") "C412369"))
      (libsource (lib "Mfd3Schlib") (part "TACT SWITCH 5.2mm"))
    )
    (comp (ref "SW15")
      (value "TACT SWITCH 5.2mm")
      (footprint "TACT SWITCH 5.2mm")
      (description "Push button 5.2 mm")
      (fields (field (name "LCSC PART #") "C412369"))
      (libsource (lib "Mfd3Schlib") (part "TACT SWITCH 5.2mm"))
    )
    (comp (ref "SW16")
      (value "TACT SWITCH 5.2mm")
      (footprint "TACT SWITCH 5.2mm")
      (description "Push button 5.2 mm")
      (fields (field (name "LCSC PART #") "C412369"))
      (libsource (lib "Mfd3Schlib") (part "TACT SWITCH 5.2mm"))
    )
    (comp (ref "SW17")
      (value "TACT SWITCH 5.2mm")
      (footprint "TACT SWITCH 5.2mm")
      (description "Push button 5.2 mm")
      (fields (field (name "LCSC PART #") "C412369"))
      (libsource (lib "Mfd3Schlib") (part "TACT SWITCH 5.2mm"))
    )
    (comp (ref "SW18")
      (value "TACT SWITCH 5.2mm")
      (footprint "TACT SWITCH 5.2mm")
      (description "Push button 5.2 mm")
      (fields (field (name "LCSC PART #") "C412369"))
      (libsource (lib "Mfd3Schlib") (part "TACT SWITCH 5.2mm"))
    )
    (comp (ref "SW19")
      (value "TACT SWITCH 5.2mm")
      (footprint "TACT SWITCH 5.2mm")
      (description "Push button 5.2 mm")
      (fields (field (name "LCSC PART #") "C412369"))
      (libsource (lib "Mfd3Schlib") (part "TACT SWITCH 5.2mm"))
    )
    (comp (ref "SW20")
      (value "TACT SWITCH 5.2mm")
      (footprint "TACT SWITCH 5.2mm")
      (description "Push button 5.2 mm")
      (fields (field (name "LCSC PART #") "C412369"))
      (libsource (lib "Mfd3Schlib") (part "TACT SWITCH 5.2mm"))
    )
    (comp (ref "SW21")
      (value "TACT SWITCH 5.2mm")
      (footprint "TACT SWITCH 5.2mm")
      (description "Push button 5.2 mm")
      (fields (field (name "LCSC PART #") "C412369"))
      (libsource (lib "Mfd3Schlib") (part "TACT SWITCH 5.2mm"))
    )
    (comp (ref "SW22")
      (value "TACT SWITCH 5.2mm")
      (footprint "TACT SWITCH 5.2mm")
      (description "Push button 5.2 mm")
      (fields (field (name "LCSC PART #") "C412369"))
      (libsource (lib "Mfd3Schlib") (part "TACT SWITCH 5.2mm"))
    )
    (comp (ref "SW23")
      (value "TACT SWITCH 5.2mm")
      (footprint "TACT SWITCH 5.2mm")
      (description "Push button 5.2 mm")
      (fields (field (name "LCSC PART #") "C412369"))
      (libsource (lib "Mfd3Schlib") (part "TACT SWITCH 5.2mm"))
    )
    (comp (ref "SW24")
      (value "TACT SWITCH 5.2mm")
      (footprint "TACT SWITCH 5.2mm")
      (description "Push button 5.2 mm")
      (fields (field (name "LCSC PART #") "C412369"))
      (libsource (lib "Mfd3Schlib") (part "TACT SWITCH 5.2mm"))
    )
    (comp (ref "SW25")
      (value "TACT SWITCH 5.2mm")
      (footprint "TACT SWITCH 5.2mm")
      (description "Push button 5.2 mm")
      (fields (field (name "LCSC PART #") "C412369"))
      (libsource (lib "Mfd3Schlib") (part "TACT SWITCH 5.2mm"))
    )
    (comp (ref "SW26")
      (value "TACT SWITCH 5.2mm")
      (footprint "TACT SWITCH 5.2mm")
      (description "Push button 5.2 mm")
      (fields (field (name "LCSC PART #") "C412369"))
      (libsource (lib "Mfd3Schlib") (part "TACT SWITCH 5.2mm"))
    )
    (comp (ref "SW27")
      (value "TACT SWITCH 5.2mm")
      (footprint "TACT SWITCH 5.2mm")
      (description "Push button 5.2 mm")
      (fields (field (name "LCSC PART #") "C412369"))
      (libsource (lib "Mfd3Schlib") (part "TACT SWITCH 5.2mm"))
    )
    (comp (ref "SW28")
      (value "TACT SWITCH 5.2mm")
      (footprint "TACT SWITCH 5.2mm")
      (description "Push button 5.2 mm")
      (fields (field (name "LCSC PART #") "C412369"))
      (libsource (lib "Mfd3Schlib") (part "TACT SWITCH 5.2mm"))
    )
    (comp (ref "SW29")
      (value "TACT SWITCH 5.2mm")
      (footprint "TACT SWITCH 5.2mm")
      (description "Push button 5.2 mm")
      (fields (field (name "LCSC PART #") "C412369"))
      (libsource (lib "Mfd3Schlib") (part "TACT SWITCH 5.2mm"))
    )
    (comp (ref "SW30")
      (value "TACT SWITCH 5.2mm")
      (footprint "TACT SWITCH 5.2mm")
      (description "Push button 5.2 mm")
      (fields (field (name "LCSC PART #") "C412369"))
      (libsource (lib "Mfd3Schlib") (part "TACT SWITCH 5.2mm"))
    )
    (comp (ref "SW31")
      (value "TACT SWITCH 5.2mm")
      (footprint "TACT SWITCH 5.2mm")
      (description "Push button 5.2 mm")
      (fields (field (name "LCSC PART #") "C412369"))
      (libsource (lib "Mfd3Schlib") (part "TACT SWITCH 5.2mm"))
    )
    (comp (ref "SW32")
      (value "TACT SWITCH 5.2mm")
      (footprint "TACT SWITCH 5.2mm")
      (description "Push button 5.2 mm")
      (fields (field (name "LCSC PART #") "C412369"))
      (libsource (lib "Mfd3Schlib") (part "TACT SWITCH 5.2mm"))
    )
    (comp (ref "SW33")
      (value "TACT SWITCH 5.2mm")
      (footprint "TACT SWITCH 5.2mm")
      (description "Push button 5.2 mm")
      (fields (field (name "LCSC PART #") "C412369"))
      (libsource (lib "Mfd3Schlib") (part "TACT SWITCH 5.2mm"))
    )
    (comp (ref "SW34")
      (value "TACT SWITCH 5.2mm")
      (footprint "TACT SWITCH 5.2mm")
      (description "Push button 5.2 mm")
      (fields (field (name "LCSC PART #") "C412369"))
      (libsource (lib "Mfd3Schlib") (part "TACT SWITCH 5.2mm"))
    )
    (comp (ref "SW35")
      (value "~")
      (footprint "PushButton")
      (description "WS-TASV SMD Tact Switch 6.0X3.5 mm")
      (fields (field (name "PARTNUMBER") "434121050816") (field (name "MANUFACTURER") "Wuerth Elektronik"))
      (libsource (lib "Mfd3Schlib") (part "Pushbutton"))
    )
    (comp (ref "U1")
      (value "74HC165D,653")
      (footprint "SOIC-16")
      (description "8-Bit Parallel-Load Shift Registers, SOIC-16, LARGE T&R")
      (fields (field (name "LCSC PART #") "C5613"))
      (libsource (lib "MfdSchlib") (part "74HC165"))
    )
    (comp (ref "U2")
      (value "74HC165D,653")
      (footprint "SOIC-16")
      (description "8-Bit Parallel-Load Shift Registers, SOIC-16, LARGE T&R")
      (fields (field (name "LCSC PART #") "C5613"))
      (libsource (lib "MfdSchlib") (part "74HC165"))
    )
    (comp (ref "U3")
      (value "74HC165D,653")
      (footprint "SOIC-16")
      (description "8-Bit Parallel-Load Shift Registers, SOIC-16, LARGE T&R")
      (fields (field (name "LCSC PART #") "C5613"))
      (libsource (lib "MfdSchlib") (part "74HC165"))
    )
    (comp (ref "U4")
      (value "74HC165D,653")
      (footprint "SOIC-16")
      (description "8-Bit Parallel-Load Shift Registers, SOIC-16, LARGE T&R")
      (fields (field (name "LCSC PART #") "C5613"))
      (libsource (lib "MfdSchlib") (part "74HC165"))
    )
    (comp (ref "U5")
      (value "STM32F103C8T6")
      (footprint "STM-LQFP48_N")
      (fields (field (name "LCSC PART #") "C8734"))
      (libsource (lib "Mfd3Schlib") (part "STM32F103C8T6"))
    )
    (comp (ref "U6")
      (value "AMS1117-3.3")
      (footprint "FP-AMS1117-IPC_A")
      (description "LDO Voltage Regulators 1A, 3.3V")
      (fields (field (name "LCSC PART #") "C6186"))
      (libsource (lib "Mfd3Schlib") (part "AMS1117-3.3"))
    )
    (comp (ref "W0")
      (value "0R")
      (footprint "1206")
      (description "Resistor 1206")
      (fields (field (name "LCSC PART #") "C17888"))
      (libsource (lib "MfdSchlib") (part "Resistor"))
    )
    (comp (ref "W1")
      (value "0R")
      (footprint "1206")
      (description "Resistor 1206")
      (fields (field (name "LCSC PART #") "C17888"))
      (libsource (lib "MfdSchlib") (part "Resistor"))
    )
    (comp (ref "X1")
      (value "8MHz")
      (footprint "ABRA-ABM3-2_V")
      (description "Miniature Ceramic Crystal, 8 MHz, -40 to 85 degC, 2-Pin SMD, RoHS, Tape and Reel")
      (fields (field (name "LCSC PART #") "C115962"))
      (libsource (lib "Mfd3Schlib") (part "8MHz"))
    )
  )
  (nets
    (net (code "1") (name "+3.3") (class "Default")
      (node (ref "C1") (pin "2") (pinfunction "2_2") (pintype "passive"))
      (node (ref "C11") (pin "2") (pinfunction "2_2") (pintype "passive"))
      (node (ref "C12") (pin "2") (pinfunction "2_2") (pintype "passive"))
      (node (ref "C13") (pin "2") (pinfunction "2_2") (pintype "passive"))
      (node (ref "C14") (pin "2") (pinfunction "2_2") (pintype "passive"))
      (node (ref "C15") (pin "2") (pinfunction "2_2") (pintype "passive"))
      (node (ref "C17") (pin "1") (pinfunction "1_1") (pintype "passive"))
      (node (ref "C2") (pin "2") (pinfunction "2_2") (pintype "passive"))
      (node (ref "C3") (pin "2") (pinfunction "2_2") (pintype "passive"))
      (node (ref "C4") (pin "2") (pinfunction "2_2") (pintype "passive"))
      (node (ref "P2") (pin "1") (pinfunction "1_1") (pintype "passive"))
      (node (ref "R10") (pin "2") (pinfunction "2_2") (pintype "passive"))
      (node (ref "R12") (pin "2") (pinfunction "2_2") (pintype "passive"))
      (node (ref "R14") (pin "2") (pinfunction "2_2") (pintype "passive"))
      (node (ref "R16") (pin "2") (pinfunction "2_2") (pintype "passive"))
      (node (ref "R18") (pin "2") (pinfunction "2_2") (pintype "passive"))
      (node (ref "R2") (pin "2") (pinfunction "2_2") (pintype "passive"))
      (node (ref "R20") (pin "2") (pinfunction "2_2") (pintype "passive"))
      (node (ref "R22") (pin "2") (pinfunction "2_2") (pintype "passive"))
      (node (ref "R24") (pin "2") (pinfunction "2_2") (pintype "passive"))
      (node (ref "R26") (pin "2") (pinfunction "2_2") (pintype "passive"))
      (node (ref "R28") (pin "2") (pinfunction "2_2") (pintype "passive"))
      (node (ref "R30") (pin "2") (pinfunction "2_2") (pintype "passive"))
      (node (ref "R32") (pin "2") (pinfunction "2_2") (pintype "passive"))
      (node (ref "R34") (pin "2") (pinfunction "2_2") (pintype "passive"))
      (node (ref "R36") (pin "2") (pinfunction "2_2") (pintype "passive"))
      (node (ref "R38") (pin "2") (pinfunction "2_2") (pintype "passive"))
      (node (ref "R4") (pin "2") (pinfunction "2_2") (pintype "passive"))
      (node (ref "R40") (pin "2") (pinfunction "2_2") (pintype "passive"))
      (node (ref "R42") (pin "2") (pinfunction "2_2") (pintype "passive"))
      (node (ref "R44") (pin "2") (pinfunction "2_2") (pintype "passive"))
      (node (ref "R46") (pin "2") (pinfunction "2_2") (pintype "passive"))
      (node (ref "R48") (pin "2") (pinfunction "2_2") (pintype "passive"))
      (node (ref "R50") (pin "2") (pinfunction "2_2") (pintype "passive"))
      (node (ref "R52") (pin "2") (pinfunction "2_2") (pintype "passive"))
      (node (ref "R54") (pin "2") (pinfunction "2_2") (pintype "passive"))
      (node (ref "R56") (pin "2") (pinfunction "2_2") (pintype "passive"))
      (node (ref "R58") (pin "2") (pinfunction "2_2") (pintype "passive"))
      (node (ref "R6") (pin "2") (pinfunction "2_2") (pintype "passive"))
      (node (ref "R60") (pin "2") (pinfunction "2_2") (pintype "passive"))
      (node (ref "R62") (pin "2") (pinfunction "2_2") (pintype "passive"))
      (node (ref "R64") (pin "2") (pinfunction "2_2") (pintype "passive"))
      (node (ref "R66") (pin "2") (pinfunction "2_2") (pintype "passive"))
      (node (ref "R68") (pin "2") (pinfunction "2_2") (pintype "passive"))
      (node (ref "R74") (pin "1") (pinfunction "1_1") (pintype "passive"))
      (node (ref "R76") (pin "1") (pinfunction "1_1") (pintype "passive"))
      (node (ref "R78") (pin "2") (pinfunction "2_2") (pintype "passive"))
      (node (ref "R8") (pin "2") (pinfunction "2_2") (pintype "passive"))
      (node (ref "SW1") (pin "4") (pinfunction "4_4") (pintype "passive"))
      (node (ref "SW10") (pin "4") (pinfunction "4_4") (pintype "passive"))
      (node (ref "SW11") (pin "4") (pinfunction "4_4") (pintype "passive"))
      (node (ref "SW12") (pin "4") (pinfunction "4_4") (pintype "passive"))
      (node (ref "SW13") (pin "4") (pinfunction "4_4") (pintype "passive"))
      (node (ref "SW14") (pin "4") (pinfunction "4_4") (pintype "passive"))
      (node (ref "SW15") (pin "4") (pinfunction "4_4") (pintype "passive"))
      (node (ref "SW16") (pin "4") (pinfunction "4_4") (pintype "passive"))
      (node (ref "SW17") (pin "4") (pinfunction "4_4") (pintype "passive"))
      (node (ref "SW18") (pin "4") (pinfunction "4_4") (pintype "passive"))
      (node (ref "SW19") (pin "4") (pinfunction "4_4") (pintype "passive"))
      (node (ref "SW2") (pin "4") (pinfunction "4_4") (pintype "passive"))
      (node (ref "SW20") (pin "4") (pinfunction "4_4") (pintype "passive"))
      (node (ref "SW21") (pin "4") (pinfunction "4_4") (pintype "passive"))
      (node (ref "SW22") (pin "4") (pinfunction "4_4") (pintype "passive"))
      (node (ref "SW23") (pin "4") (pinfunction "4_4") (pintype "passive"))
      (node (ref "SW24") (pin "4") (pinfunction "4_4") (pintype "passive"))
      (node (ref "SW25") (pin "4") (pinfunction "4_4") (pintype "passive"))
      (node (ref "SW26") (pin "4") (pinfunction "4_4") (pintype "passive"))
      (node (ref "SW27") (pin "4") (pinfunction "4_4") (pintype "passive"))
      (node (ref "SW28") (pin "4") (pinfunction "4_4") (pintype "passive"))
      (node (ref "SW29") (pin "4") (pinfunction "4_4") (pintype "passive"))
      (node (ref "SW3") (pin "4") (pinfunction "4_4") (pintype "passive"))
      (node (ref "SW30") (pin "4") (pinfunction "4_4") (pintype "passive"))
      (node (ref "SW31") (pin "4") (pinfunction "4_4") (pintype "passive"))
      (node (ref "SW32") (pin "4") (pinfunction "4_4") (pintype "passive"))
      (node (ref "SW33") (pin "4") (pinfunction "4_4") (pintype "passive"))
      (node (ref "SW34") (pin "4") (pinfunction "4_4") (pintype "passive"))
      (node (ref "SW4") (pin "4") (pinfunction "4_4") (pintype "passive"))
      (node (ref "SW5") (pin "4") (pinfunction "4_4") (pintype "passive"))
      (node (ref "SW6") (pin "4") (pinfunction "4_4") (pintype "passive"))
      (node (ref "SW7") (pin "4") (pinfunction "4_4") (pintype "passive"))
      (node (ref "SW8") (pin "4") (pinfunction "4_4") (pintype "passive"))
      (node (ref "SW9") (pin "4") (pinfunction "4_4") (pintype "passive"))
      (node (ref "U1") (pin "16") (pinfunction "VCC_16") (pintype "power_in"))
      (node (ref "U2") (pin "16") (pinfunction "VCC_16") (pintype "power_in"))
      (node (ref "U3") (pin "16") (pinfunction "VCC_16") (pintype "power_in"))
      (node (ref "U4") (pin "16") (pinfunction "VCC_16") (pintype "power_in"))
      (node (ref "U5") (pin "24") (pinfunction "VDD_1_24") (pintype "power_in"))
      (node (ref "U5") (pin "36") (pinfunction "VDD_2_36") (pintype "power_in"))
      (node (ref "U5") (pin "48") (pinfunction "VDD_3_48") (pintype "power_in"))
      (node (ref "U5") (pin "9") (pinfunction "VDDA_9") (pintype "power_in"))
      (node (ref "U6") (pin "2") (pinfunction "VOUT_2") (pintype "passive"))
      (node (ref "U6") (pin "4") (pinfunction "VOUT_4") (pintype "passive"))
    )
    (net (code "2") (name "+5") (class "Default")
      (node (ref "C10") (pin "2") (pinfunction "2_2") (pintype "passive"))
      (node (ref "C16") (pin "1") (pinfunction "1_1") (pintype "passive"))
      (node (ref "P4") (pin "1") (pinfunction "VBUS_1") (pintype "passive"))
      (node (ref "P7") (pin "1") (pinfunction "1_1") (pintype "passive"))
      (node (ref "U6") (pin "3") (pinfunction "VIN_3") (pintype "power_in"))
    )
    (net (code "3") (name "/B4") (class "Default")
      (node (ref "R51") (pin "2") (pinfunction "2_2") (pintype "passive"))
      (node (ref "SW26") (pin "1") (pinfunction "1_1") (pintype "passive"))
      (node (ref "U5") (pin "22") (pinfunction "PB11_22") (pintype "bidirectional"))
    )
    (net (code "4") (name "/B6") (class "Default")
      (node (ref "R1") (pin "2") (pinfunction "2_2") (pintype "passive"))
      (node (ref "SW1") (pin "1") (pinfunction "1_1") (pintype "passive"))
      (node (ref "U5") (pin "21") (pinfunction "PB10_21") (pintype "bidirectional"))
    )
    (net (code "5") (name "/BOOT0") (class "Default")
      (node (ref "R70") (pin "1") (pinfunction "1_1") (pintype "passive"))
      (node (ref "W0") (pin "2") (pinfunction "2_2") (pintype "passive"))
    )
    (net (code "6") (name "/BOOT1") (class "Default")
      (node (ref "R75") (pin "1") (pinfunction "1_1") (pintype "passive"))
      (node (ref "W1") (pin "2") (pinfunction "2_2") (pintype "passive"))
    )
    (net (code "7") (name "/CLK") (class "Default")
      (node (ref "U1") (pin "2") (pinfunction "CLK_2") (pintype "input"))
      (node (ref "U2") (pin "2") (pinfunction "CLK_2") (pintype "input"))
      (node (ref "U3") (pin "2") (pinfunction "CLK_2") (pintype "input"))
      (node (ref "U4") (pin "2") (pinfunction "CLK_2") (pintype "input"))
      (node (ref "U5") (pin "39") (pinfunction "PB3_39") (pintype "bidirectional"))
    )
    (net (code "8") (name "/D1_N") (class "Default")
      (node (ref "R71") (pin "2") (pinfunction "2_2") (pintype "passive"))
      (node (ref "U5") (pin "32") (pinfunction "PA11_32") (pintype "bidirectional"))
    )
    (net (code "9") (name "/D1_P") (class "Default")
      (node (ref "R72") (pin "2") (pinfunction "2_2") (pintype "passive"))
      (node (ref "U5") (pin "33") (pinfunction "PA12_33") (pintype "bidirectional"))
    )
    (net (code "10") (name "/D_N") (class "Default")
      (node (ref "P4") (pin "2") (pinfunction "D-_2") (pintype "passive"))
      (node (ref "P7") (pin "2") (pinfunction "2_2") (pintype "passive"))
      (node (ref "R71") (pin "1") (pinfunction "1_1") (pintype "passive"))
    )
    (net (code "11") (name "/D_P") (class "Default")
      (node (ref "P4") (pin "3") (pinfunction "D+_3") (pintype "passive"))
      (node (ref "P7") (pin "3") (pinfunction "3_3") (pintype "passive"))
      (node (ref "R72") (pin "1") (pinfunction "1_1") (pintype "passive"))
      (node (ref "R74") (pin "2") (pinfunction "2_2") (pintype "passive"))
    )
    (net (code "12") (name "/PL") (class "Default")
      (node (ref "U1") (pin "1") (pinfunction "~{PL}_1") (pintype "input"))
      (node (ref "U2") (pin "1") (pinfunction "~{PL}_1") (pintype "input"))
      (node (ref "U3") (pin "1") (pinfunction "~{PL}_1") (pintype "input"))
      (node (ref "U4") (pin "1") (pinfunction "~{PL}_1") (pintype "input"))
      (node (ref "U5") (pin "46") (pinfunction "PB9_46") (pintype "bidirectional"))
    )
    (net (code "13") (name "/RX") (class "Default")
      (node (ref "P3") (pin "2") (pinfunction "2_2") (pintype "passive"))
      (node (ref "U5") (pin "31") (pinfunction "PA10_31") (pintype "bidirectional"))
    )
    (net (code "14") (name "/SWCLK") (class "Default")
      (node (ref "P2") (pin "3") (pinfunction "3_3") (pintype "passive"))
      (node (ref "R78") (pin "1") (pinfunction "1_1") (pintype "passive"))
      (node (ref "U5") (pin "37") (pinfunction "PA14_37") (pintype "bidirectional"))
    )
    (net (code "15") (name "/SWDIO") (class "Default")
      (node (ref "P2") (pin "2") (pinfunction "2_2") (pintype "passive"))
      (node (ref "R77") (pin "2") (pinfunction "2_2") (pintype "passive"))
      (node (ref "U5") (pin "34") (pinfunction "PA13_34") (pintype "bidirectional"))
    )
    (net (code "16") (name "/TX") (class "Default")
      (node (ref "P3") (pin "1") (pinfunction "1_1") (pintype "passive"))
      (node (ref "U5") (pin "30") (pinfunction "PA9_30") (pintype "bidirectional"))
    )
    (net (code "17") (name "/U1_QH") (class "Default")
      (node (ref "U1") (pin "9") (pinfunction "QH_9") (pintype "output"))
      (node (ref "U5") (pin "25") (pinfunction "PB12_25") (pintype "bidirectional"))
    )
    (net (code "18") (name "/U2_QH") (class "Default")
      (node (ref "U2") (pin "9") (pinfunction "QH_9") (pintype "output"))
      (node (ref "U4") (pin "10") (pinfunction "DS_10") (pintype "input"))
    )
    (net (code "19") (name "/U3_QH") (class "Default")
      (node (ref "U1") (pin "10") (pinfunction "DS_10") (pintype "input"))
      (node (ref "U3") (pin "9") (pinfunction "QH_9") (pintype "output"))
    )
    (net (code "20") (name "/U4_QH") (class "Default")
      (node (ref "U3") (pin "10") (pinfunction "DS_10") (pintype "input"))
      (node (ref "U4") (pin "9") (pinfunction "QH_9") (pintype "output"))
    )
    (net (code "21") (name "GND") (class "Default")
      (node (ref "C1") (pin "1") (pinfunction "1_1") (pintype "passive"))
      (node (ref "C10") (pin "1") (pinfunction "1_1") (pintype "passive"))
      (node (ref "C11") (pin "1") (pinfunction "1_1") (pintype "passive"))
      (node (ref "C12") (pin "1") (pinfunction "1_1") (pintype "passive"))
      (node (ref "C13") (pin "1") (pinfunction "1_1") (pintype "passive"))
      (node (ref "C14") (pin "1") (pinfunction "1_1") (pintype "passive"))
      (node (ref "C15") (pin "1") (pinfunction "1_1") (pintype "passive"))
      (node (ref "C16") (pin "2") (pinfunction "2_2") (pintype "passive"))
      (node (ref "C17") (pin "2") (pinfunction "2_2") (pintype "passive"))
      (node (ref "C2") (pin "1") (pinfunction "1_1") (pintype "passive"))
      (node (ref "C3") (pin "1") (pinfunction "1_1") (pintype "passive"))
      (node (ref "C4") (pin "1") (pinfunction "1_1") (pintype "passive"))
      (node (ref "C7") (pin "2") (pinfunction "2_2") (pintype "passive"))
      (node (ref "C8") (pin "1") (pinfunction "1_1") (pintype "passive"))
      (node (ref "C9") (pin "2") (pinfunction "2_2") (pintype "passive"))
      (node (ref "LED1") (pin "2") (pinfunction "K_2") (pintype "passive"))
      (node (ref "LED10") (pin "2") (pinfunction "K_2") (pintype "passive"))
      (node (ref "LED11") (pin "2") (pinfunction "K_2") (pintype "passive"))
      (node (ref "LED12") (pin "2") (pinfunction "K_2") (pintype "passive"))
      (node (ref "LED13") (pin "2") (pinfunction "K_2") (pintype "passive"))
      (node (ref "LED14") (pin "2") (pinfunction "K_2") (pintype "passive"))
      (node (ref "LED15") (pin "2") (pinfunction "K_2") (pintype "passive"))
      (node (ref "LED16") (pin "2") (pinfunction "K_2") (pintype "passive"))
      (node (ref "LED17") (pin "2") (pinfunction "K_2") (pintype "passive"))
      (node (ref "LED18") (pin "2") (pinfunction "K_2") (pintype "passive"))
      (node (ref "LED19") (pin "2") (pinfunction "K_2") (pintype "passive"))
      (node (ref "LED2") (pin "2") (pinfunction "K_2") (pintype "passive"))
      (node (ref "LED20") (pin "2") (pinfunction "K_2") (pintype "passive"))
      (node (ref "LED21") (pin "2") (pinfunction "K_2") (pintype "passive"))
      (node (ref "LED22") (pin "2") (pinfunction "K_2") (pintype "passive"))
      (node (ref "LED23") (pin "2") (pinfunction "K_2") (pintype "passive"))
      (node (ref "LED24") (pin "2") (pinfunction "K_2") (pintype "passive"))
      (node (ref "LED25") (pin "2") (pinfunction "K_2") (pintype "passive"))
      (node (ref "LED26") (pin "2") (pinfunction "K_2") (pintype "passive"))
      (node (ref "LED27") (pin "2") (pinfunction "K_2") (pintype "passive"))
      (node (ref "LED28") (pin "2") (pinfunction "K_2") (pintype "passive"))
      (node (ref "LED29") (pin "2") (pinfunction "K_2") (pintype "passive"))
      (node (ref "LED3") (pin "2") (pinfunction "K_2") (pintype "passive"))
      (node (ref "LED30") (pin "2") (pinfunction "K_2") (pintype "passive"))
      (node (ref "LED31") (pin "2") (pinfunction "K_2") (pintype "passive"))
      (node (ref "LED32") (pin "2") (pinfunction "K_2") (pintype "passive"))
      (node (ref "LED33") (pin "2") (pinfunction "K_2") (pintype "passive"))
      (node (ref "LED34") (pin "2") (pinfunction "K_2") (pintype "passive"))
      (node (ref "LED4") (pin "2") (pinfunction "K_2") (pintype "passive"))
      (node (ref "LED5") (pin "2") (pinfunction "K_2") (pintype "passive"))
      (node (ref "LED6") (pin "2") (pinfunction "K_2") (pintype "passive"))
      (node (ref "LED7") (pin "2") (pinfunction "K_2") (pintype "passive"))
      (node (ref "LED8") (pin "2") (pinfunction "K_2") (pintype "passive"))
      (node (ref "LED9") (pin "2") (pinfunction "K_2") (pintype "passive"))
      (node (ref "P2") (pin "4") (pinfunction "4_4") (pintype "passive"))
      (node (ref "P3") (pin "3") (pinfunction "3_3") (pintype "passive"))
      (node (ref "P4") (pin "4") (pinfunction "GND_4") (pintype "passive"))
      (node (ref "P7") (pin "4") (pinfunction "4_4") (pintype "passive"))
      (node (ref "R1") (pin "1") (pinfunction "1_1") (pintype "passive"))
      (node (ref "R11") (pin "1") (pinfunction "1_1") (pintype "passive"))
      (node (ref "R13") (pin "1") (pinfunction "1_1") (pintype "passive"))
      (node (ref "R15") (pin "1") (pinfunction "1_1") (pintype "passive"))
      (node (ref "R17") (pin "1") (pinfunction "1_1") (pintype "passive"))
      (node (ref "R19") (pin "1") (pinfunction "1_1") (pintype "passive"))
      (node (ref "R21") (pin "1") (pinfunction "1_1") (pintype "passive"))
      (node (ref "R23") (pin "1") (pinfunction "1_1") (pintype "passive"))
      (node (ref "R25") (pin "1") (pinfunction "1_1") (pintype "passive"))
      (node (ref "R27") (pin "1") (pinfunction "1_1") (pintype "passive"))
      (node (ref "R29") (pin "1") (pinfunction "1_1") (pintype "passive"))
      (node (ref "R3") (pin "1") (pinfunction "1_1") (pintype "passive"))
      (node (ref "R31") (pin "1") (pinfunction "1_1") (pintype "passive"))
      (node (ref "R33") (pin "1") (pinfunction "1_1") (pintype "passive"))
      (node (ref "R35") (pin "1") (pinfunction "1_1") (pintype "passive"))
      (node (ref "R37") (pin "1") (pinfunction "1_1") (pintype "passive"))
      (node (ref "R39") (pin "1") (pinfunction "1_1") (pintype "passive"))
      (node (ref "R41") (pin "1") (pinfunction "1_1") (pintype "passive"))
      (node (ref "R43") (pin "1") (pinfunction "1_1") (pintype "passive"))
      (node (ref "R45") (pin "1") (pinfunction "1_1") (pintype "passive"))
      (node (ref "R47") (pin "1") (pinfunction "1_1") (pintype "passive"))
      (node (ref "R49") (pin "1") (pinfunction "1_1") (pintype "passive"))
      (node (ref "R5") (pin "1") (pinfunction "1_1") (pintype "passive"))
      (node (ref "R51") (pin "1") (pinfunction "1_1") (pintype "passive"))
      (node (ref "R53") (pin "1") (pinfunction "1_1") (pintype "passive"))
      (node (ref "R55") (pin "1") (pinfunction "1_1") (pintype "passive"))
      (node (ref "R57") (pin "1") (pinfunction "1_1") (pintype "passive"))
      (node (ref "R59") (pin "1") (pinfunction "1_1") (pintype "passive"))
      (node (ref "R61") (pin "1") (pinfunction "1_1") (pintype "passive"))
      (node (ref "R63") (pin "1") (pinfunction "1_1") (pintype "passive"))
      (node (ref "R65") (pin "1") (pinfunction "1_1") (pintype "passive"))
      (node (ref "R67") (pin "1") (pinfunction "1_1") (pintype "passive"))
      (node (ref "R7") (pin "1") (pinfunction "1_1") (pintype "passive"))
      (node (ref "R77") (pin "1") (pinfunction "1_1") (pintype "passive"))
      (node (ref "R9") (pin "1") (pinfunction "1_1") (pintype "passive"))
      (node (ref "SW35") (pin "2") (pinfunction "2_2") (pintype "passive"))
      (node (ref "U1") (pin "15") (pinfunction "~{CE}_15") (pintype "input"))
      (node (ref "U1") (pin "8") (pinfunction "GND_8") (pintype "power_in"))
      (node (ref "U2") (pin "10") (pinfunction "DS_10") (pintype "input"))
      (node (ref "U2") (pin "15") (pinfunction "~{CE}_15") (pintype "input"))
      (node (ref "U2") (pin "8") (pinfunction "GND_8") (pintype "power_in"))
      (node (ref "U3") (pin "15") (pinfunction "~{CE}_15") (pintype "input"))
      (node (ref "U3") (pin "8") (pinfunction "GND_8") (pintype "power_in"))
      (node (ref "U4") (pin "15") (pinfunction "~{CE}_15") (pintype "input"))
      (node (ref "U4") (pin "8") (pinfunction "GND_8") (pintype "power_in"))
      (node (ref "U5") (pin "23") (pinfunction "VSS_1_23") (pintype "power_in"))
      (node (ref "U5") (pin "35") (pinfunction "VSS_2_35") (pintype "power_in"))
      (node (ref "U5") (pin "47") (pinfunction "VSS_3_47") (pintype "power_in"))
      (node (ref "U5") (pin "8") (pinfunction "VSSA_8") (pintype "power_in"))
      (node (ref "U6") (pin "1") (pinfunction "Ground_1") (pintype "power_in"))
      (node (ref "W0") (pin "1") (pinfunction "1_1") (pintype "passive"))
      (node (ref "W1") (pin "1") (pinfunction "1_1") (pintype "passive"))
    )
    (net (code "22") (name "Net-(LED1-A)") (class "Default")
      (node (ref "LED1") (pin "1") (pinfunction "A_1") (pintype "passive"))
      (node (ref "R2") (pin "1") (pinfunction "1_1") (pintype "passive"))
    )
    (net (code "23") (name "Net-(LED2-A)") (class "Default")
      (node (ref "LED2") (pin "1") (pinfunction "A_1") (pintype "passive"))
      (node (ref "R4") (pin "1") (pinfunction "1_1") (pintype "passive"))
    )
    (net (code "24") (name "Net-(LED3-A)") (class "Default")
      (node (ref "LED3") (pin "1") (pinfunction "A_1") (pintype "passive"))
      (node (ref "R6") (pin "1") (pinfunction "1_1") (pintype "passive"))
    )
    (net (code "25") (name "Net-(LED4-A)") (class "Default")
      (node (ref "LED4") (pin "1") (pinfunction "A_1") (pintype "passive"))
      (node (ref "R8") (pin "1") (pinfunction "1_1") (pintype "passive"))
    )
    (net (code "26") (name "Net-(LED5-A)") (class "Default")
      (node (ref "LED5") (pin "1") (pinfunction "A_1") (pintype "passive"))
      (node (ref "R10") (pin "1") (pinfunction "1_1") (pintype "passive"))
    )
    (net (code "27") (name "Net-(LED6-A)") (class "Default")
      (node (ref "LED6") (pin "1") (pinfunction "A_1") (pintype "passive"))
      (node (ref "R12") (pin "1") (pinfunction "1_1") (pintype "passive"))
    )
    (net (code "28") (name "Net-(LED7-A)") (class "Default")
      (node (ref "LED7") (pin "1") (pinfunction "A_1") (pintype "passive"))
      (node (ref "R14") (pin "1") (pinfunction "1_1") (pintype "passive"))
    )
    (net (code "29") (name "Net-(LED8-A)") (class "Default")
      (node (ref "LED8") (pin "1") (pinfunction "A_1") (pintype "passive"))
      (node (ref "R16") (pin "1") (pinfunction "1_1") (pintype "passive"))
    )
    (net (code "30") (name "Net-(LED9-A)") (class "Default")
      (node (ref "LED9") (pin "1") (pinfunction "A_1") (pintype "passive"))
      (node (ref "R18") (pin "1") (pinfunction "1_1") (pintype "passive"))
    )
    (net (code "31") (name "Net-(LED10-A)") (class "Default")
      (node (ref "LED10") (pin "1") (pinfunction "A_1") (pintype "passive"))
      (node (ref "R34") (pin "1") (pinfunction "1_1") (pintype "passive"))
    )
    (net (code "32") (name "Net-(LED11-A)") (class "Default")
      (node (ref "LED11") (pin "1") (pinfunction "A_1") (pintype "passive"))
      (node (ref "R32") (pin "1") (pinfunction "1_1") (pintype "passive"))
    )
    (net (code "33") (name "Net-(LED12-A)") (class "Default")
      (node (ref "LED12") (pin "1") (pinfunction "A_1") (pintype "passive"))
      (node (ref "R30") (pin "1") (pinfunction "1_1") (pintype "passive"))
    )
    (net (code "34") (name "Net-(LED13-A)") (class "Default")
      (node (ref "LED13") (pin "1") (pinfunction "A_1") (pintype "passive"))
      (node (ref "R28") (pin "1") (pinfunction "1_1") (pintype "passive"))
    )
    (net (code "35") (name "Net-(LED14-A)") (class "Default")
      (node (ref "LED14") (pin "1") (pinfunction "A_1") (pintype "passive"))
      (node (ref "R26") (pin "1") (pinfunction "1_1") (pintype "passive"))
    )
    (net (code "36") (name "Net-(LED15-A)") (class "Default")
      (node (ref "LED15") (pin "1") (pinfunction "A_1") (pintype "passive"))
      (node (ref "R24") (pin "1") (pinfunction "1_1") (pintype "passive"))
    )
    (net (code "37") (name "Net-(LED16-A)") (class "Default")
      (node (ref "LED16") (pin "1") (pinfunction "A_1") (pintype "passive"))
      (node (ref "R22") (pin "1") (pinfunction "1_1") (pintype "passive"))
    )
    (net (code "38") (name "Net-(LED17-A)") (class "Default")
      (node (ref "LED17") (pin "1") (pinfunction "A_1") (pintype "passive"))
      (node (ref "R20") (pin "1") (pinfunction "1_1") (pintype "passive"))
    )
    (net (code "39") (name "Net-(LED18-A)") (class "Default")
      (node (ref "LED18") (pin "1") (pinfunction "A_1") (pintype "passive"))
      (node (ref "R36") (pin "1") (pinfunction "1_1") (pintype "passive"))
    )
    (net (code "40") (name "Net-(LED19-A)") (class "Default")
      (node (ref "LED19") (pin "1") (pinfunction "A_1") (pintype "passive"))
      (node (ref "R38") (pin "1") (pinfunction "1_1") (pintype "passive"))
    )
    (net (code "41") (name "Net-(LED20-A)") (class "Default")
      (node (ref "LED20") (pin "1") (pinfunction "A_1") (pintype "passive"))
      (node (ref "R40") (pin "1") (pinfunction "1_1") (pintype "passive"))
    )
    (net (code "42") (name "Net-(LED21-A)") (class "Default")
      (node (ref "LED21") (pin "1") (pinfunction "A_1") (pintype "passive"))
      (node (ref "R42") (pin "1") (pinfunction "1_1") (pintype "passive"))
    )
    (net (code "43") (name "Net-(LED22-A)") (class "Default")
      (node (ref "LED22") (pin "1") (pinfunction "A_1") (pintype "passive"))
      (node (ref "R44") (pin "1") (pinfunction "1_1") (pintype "passive"))
    )
    (net (code "44") (name "Net-(LED23-A)") (class "Default")
      (node (ref "LED23") (pin "1") (pinfunction "A_1") (pintype "passive"))
      (node (ref "R46") (pin "1") (pinfunction "1_1") (pintype "passive"))
    )
    (net (code "45") (name "Net-(LED24-A)") (class "Default")
      (node (ref "LED24") (pin "1") (pinfunction "A_1") (pintype "passive"))
      (node (ref "R48") (pin "1") (pinfunction "1_1") (pintype "passive"))
    )
    (net (code "46") (name "Net-(LED25-A)") (class "Default")
      (node (ref "LED25") (pin "1") (pinfunction "A_1") (pintype "passive"))
      (node (ref "R50") (pin "1") (pinfunction "1_1") (pintype "passive"))
    )
    (net (code "47") (name "Net-(LED26-A)") (class "Default")
      (node (ref "LED26") (pin "1") (pinfunction "A_1") (pintype "passive"))
      (node (ref "R52") (pin "1") (pinfunction "1_1") (pintype "passive"))
    )
    (net (code "48") (name "Net-(LED27-A)") (class "Default")
      (node (ref "LED27") (pin "1") (pinfunction "A_1") (pintype "passive"))
      (node (ref "R54") (pin "1") (pinfunction "1_1") (pintype "passive"))
    )
    (net (code "49") (name "Net-(LED28-A)") (class "Default")
      (node (ref "LED28") (pin "1") (pinfunction "A_1") (pintype "passive"))
      (node (ref "R56") (pin "1") (pinfunction "1_1") (pintype "passive"))
    )
    (net (code "50") (name "Net-(LED29-A)") (class "Default")
      (node (ref "LED29") (pin "1") (pinfunction "A_1") (pintype "passive"))
      (node (ref "R58") (pin "1") (pinfunction "1_1") (pintype "passive"))
    )
    (net (code "51") (name "Net-(LED30-A)") (class "Default")
      (node (ref "LED30") (pin "1") (pinfunction "A_1") (pintype "passive"))
      (node (ref "R60") (pin "1") (pinfunction "1_1") (pintype "passive"))
    )
    (net (code "52") (name "Net-(LED31-A)") (class "Default")
      (node (ref "LED31") (pin "1") (pinfunction "A_1") (pintype "passive"))
      (node (ref "R62") (pin "1") (pinfunction "1_1") (pintype "passive"))
    )
    (net (code "53") (name "Net-(LED32-A)") (class "Default")
      (node (ref "LED32") (pin "1") (pinfunction "A_1") (pintype "passive"))
      (node (ref "R64") (pin "1") (pinfunction "1_1") (pintype "passive"))
    )
    (net (code "54") (name "Net-(LED33-A)") (class "Default")
      (node (ref "LED33") (pin "1") (pinfunction "A_1") (pintype "passive"))
      (node (ref "R66") (pin "1") (pinfunction "1_1") (pintype "passive"))
    )
    (net (code "55") (name "Net-(LED34-A)") (class "Default")
      (node (ref "LED34") (pin "1") (pinfunction "A_1") (pintype "passive"))
      (node (ref "R68") (pin "1") (pinfunction "1_1") (pintype "passive"))
    )
    (net (code "56") (name "Net-(U1-A)") (class "Default")
      (node (ref "R17") (pin "2") (pinfunction "2_2") (pintype "passive"))
      (node (ref "SW9") (pin "1") (pinfunction "1_1") (pintype "passive"))
      (node (ref "U1") (pin "11") (pinfunction "A_11") (pintype "input"))
    )
    (net (code "57") (name "Net-(U1-B)") (class "Default")
      (node (ref "R15") (pin "2") (pinfunction "2_2") (pintype "passive"))
      (node (ref "SW8") (pin "1") (pinfunction "1_1") (pintype "passive"))
      (node (ref "U1") (pin "12") (pinfunction "B_12") (pintype "input"))
    )
    (net (code "58") (name "Net-(U1-C)") (class "Default")
      (node (ref "R13") (pin "2") (pinfunction "2_2") (pintype "passive"))
      (node (ref "SW7") (pin "1") (pinfunction "1_1") (pintype "passive"))
      (node (ref "U1") (pin "13") (pinfunction "C_13") (pintype "input"))
    )
    (net (code "59") (name "Net-(U1-D)") (class "Default")
      (node (ref "R11") (pin "2") (pinfunction "2_2") (pintype "passive"))
      (node (ref "SW6") (pin "1") (pinfunction "1_1") (pintype "passive"))
      (node (ref "U1") (pin "14") (pinfunction "D_14") (pintype "input"))
    )
    (net (code "60") (name "Net-(U1-E)") (class "Default")
      (node (ref "R9") (pin "2") (pinfunction "2_2") (pintype "passive"))
      (node (ref "SW5") (pin "1") (pinfunction "1_1") (pintype "passive"))
      (node (ref "U1") (pin "3") (pinfunction "E_3") (pintype "input"))
    )
    (net (code "61") (name "Net-(U1-F)") (class "Default")
      (node (ref "R7") (pin "2") (pinfunction "2_2") (pintype "passive"))
      (node (ref "SW4") (pin "1") (pinfunction "1_1") (pintype "passive"))
      (node (ref "U1") (pin "4") (pinfunction "F_4") (pintype "input"))
    )
    (net (code "62") (name "Net-(U1-G)") (class "Default")
      (node (ref "R5") (pin "2") (pinfunction "2_2") (pintype "passive"))
      (node (ref "SW3") (pin "1") (pinfunction "1_1") (pintype "passive"))
      (node (ref "U1") (pin "5") (pinfunction "G_5") (pintype "input"))
    )
    (net (code "63") (name "Net-(U1-H)") (class "Default")
      (node (ref "R3") (pin "2") (pinfunction "2_2") (pintype "passive"))
      (node (ref "SW2") (pin "1") (pinfunction "1_1") (pintype "passive"))
      (node (ref "U1") (pin "6") (pinfunction "H_6") (pintype "input"))
    )
    (net (code "64") (name "Net-(U2-A)") (class "Default")
      (node (ref "R33") (pin "2") (pinfunction "2_2") (pintype "passive"))
      (node (ref "SW10") (pin "1") (pinfunction "1_1") (pintype "passive"))
      (node (ref "U2") (pin "11") (pinfunction "A_11") (pintype "input"))
    )
    (net (code "65") (name "Net-(U2-B)") (class "Default")
      (node (ref "R31") (pin "2") (pinfunction "2_2") (pintype "passive"))
      (node (ref "SW11") (pin "1") (pinfunction "1_1") (pintype "passive"))
      (node (ref "U2") (pin "12") (pinfunction "B_12") (pintype "input"))
    )
    (net (code "66") (name "Net-(U2-C)") (class "Default")
      (node (ref "R29") (pin "2") (pinfunction "2_2") (pintype "passive"))
      (node (ref "SW12") (pin "1") (pinfunction "1_1") (pintype "passive"))
      (node (ref "U2") (pin "13") (pinfunction "C_13") (pintype "input"))
    )
    (net (code "67") (name "Net-(U2-D)") (class "Default")
      (node (ref "R27") (pin "2") (pinfunction "2_2") (pintype "passive"))
      (node (ref "SW13") (pin "1") (pinfunction "1_1") (pintype "passive"))
      (node (ref "U2") (pin "14") (pinfunction "D_14") (pintype "input"))
    )
    (net (code "68") (name "Net-(U2-E)") (class "Default")
      (node (ref "R25") (pin "2") (pinfunction "2_2") (pintype "passive"))
      (node (ref "SW14") (pin "1") (pinfunction "1_1") (pintype "passive"))
      (node (ref "U2") (pin "3") (pinfunction "E_3") (pintype "input"))
    )
    (net (code "69") (name "Net-(U2-F)") (class "Default")
      (node (ref "R23") (pin "2") (pinfunction "2_2") (pintype "passive"))
      (node (ref "SW15") (pin "1") (pinfunction "1_1") (pintype "passive"))
      (node (ref "U2") (pin "4") (pinfunction "F_4") (pintype "input"))
    )
    (net (code "70") (name "Net-(U2-G)") (class "Default")
      (node (ref "R21") (pin "2") (pinfunction "2_2") (pintype "passive"))
      (node (ref "SW16") (pin "1") (pinfunction "1_1") (pintype "passive"))
      (node (ref "U2") (pin "5") (pinfunction "G_5") (pintype "input"))
    )
    (net (code "71") (name "Net-(U2-H)") (class "Default")
      (node (ref "R19") (pin "2") (pinfunction "2_2") (pintype "passive"))
      (node (ref "SW17") (pin "1") (pinfunction "1_1") (pintype "passive"))
      (node (ref "U2") (pin "6") (pinfunction "H_6") (pintype "input"))
    )
    (net (code "72") (name "Net-(U3-A)") (class "Default")
      (node (ref "R49") (pin "2") (pinfunction "2_2") (pintype "passive"))
      (node (ref "SW25") (pin "1") (pinfunction "1_1") (pintype "passive"))
      (node (ref "U3") (pin "11") (pinfunction "A_11") (pintype "input"))
    )
    (net (code "73") (name "Net-(U3-B)") (class "Default")
      (node (ref "R47") (pin "2") (pinfunction "2_2") (pintype "passive"))
      (node (ref "SW24") (pin "1") (pinfunction "1_1") (pintype "passive"))
      (node (ref "U3") (pin "12") (pinfunction "B_12") (pintype "input"))
    )
    (net (code "74") (name "Net-(U3-C)") (class "Default")
      (node (ref "R45") (pin "2") (pinfunction "2_2") (pintype "passive"))
      (node (ref "SW23") (pin "1") (pinfunction "1_1") (pintype "passive"))
      (node (ref "U3") (pin "13") (pinfunction "C_13") (pintype "input"))
    )
    (net (code "75") (name "Net-(U3-D)") (class "Default")
      (node (ref "R43") (pin "2") (pinfunction "2_2") (pintype "passive"))
      (node (ref "SW22") (pin "1") (pinfunction "1_1") (pintype "passive"))
      (node (ref "U3") (pin "14") (pinfunction "D_14") (pintype "input"))
    )
    (net (code "76") (name "Net-(U3-E)") (class "Default")
      (node (ref "R41") (pin "2") (pinfunction "2_2") (pintype "passive"))
      (node (ref "SW21") (pin "1") (pinfunction "1_1") (pintype "passive"))
      (node (ref "U3") (pin "3") (pinfunction "E_3") (pintype "input"))
    )
    (net (code "77") (name "Net-(U3-F)") (class "Default")
      (node (ref "R39") (pin "2") (pinfunction "2_2") (pintype "passive"))
      (node (ref "SW20") (pin "1") (pinfunction "1_1") (pintype "passive"))
      (node (ref "U3") (pin "4") (pinfunction "F_4") (pintype "input"))
    )
    (net (code "78") (name "Net-(U3-G)") (class "Default")
      (node (ref "R37") (pin "2") (pinfunction "2_2") (pintype "passive"))
      (node (ref "SW19") (pin "1") (pinfunction "1_1") (pintype "passive"))
      (node (ref "U3") (pin "5") (pinfunction "G_5") (pintype "input"))
    )
    (net (code "79") (name "Net-(U3-H)") (class "Default")
      (node (ref "R35") (pin "2") (pinfunction "2_2") (pintype "passive"))
      (node (ref "SW18") (pin "1") (pinfunction "1_1") (pintype "passive"))
      (node (ref "U3") (pin "6") (pinfunction "H_6") (pintype "input"))
    )
    (net (code "80") (name "Net-(U4-A)") (class "Default")
      (node (ref "R67") (pin "2") (pinfunction "2_2") (pintype "passive"))
      (node (ref "SW34") (pin "1") (pinfunction "1_1") (pintype "passive"))
      (node (ref "U4") (pin "11") (pinfunction "A_11") (pintype "input"))
    )
    (net (code "81") (name "Net-(U4-B)") (class "Default")
      (node (ref "R65") (pin "2") (pinfunction "2_2") (pintype "passive"))
      (node (ref "SW33") (pin "1") (pinfunction "1_1") (pintype "passive"))
      (node (ref "U4") (pin "12") (pinfunction "B_12") (pintype "input"))
    )
    (net (code "82") (name "Net-(U4-C)") (class "Default")
      (node (ref "R63") (pin "2") (pinfunction "2_2") (pintype "passive"))
      (node (ref "SW32") (pin "1") (pinfunction "1_1") (pintype "passive"))
      (node (ref "U4") (pin "13") (pinfunction "C_13") (pintype "input"))
    )
    (net (code "83") (name "Net-(U4-D)") (class "Default")
      (node (ref "R61") (pin "2") (pinfunction "2_2") (pintype "passive"))
      (node (ref "SW31") (pin "1") (pinfunction "1_1") (pintype "passive"))
      (node (ref "U4") (pin "14") (pinfunction "D_14") (pintype "input"))
    )
    (net (code "84") (name "Net-(U4-E)") (class "Default")
      (node (ref "R59") (pin "2") (pinfunction "2_2") (pintype "passive"))
      (node (ref "SW30") (pin "1") (pinfunction "1_1") (pintype "passive"))
      (node (ref "U4") (pin "3") (pinfunction "E_3") (pintype "input"))
    )
    (net (code "85") (name "Net-(U4-F)") (class "Default")
      (node (ref "R57") (pin "2") (pinfunction "2_2") (pintype "passive"))
      (node (ref "SW29") (pin "1") (pinfunction "1_1") (pintype "passive"))
      (node (ref "U4") (pin "4") (pinfunction "F_4") (pintype "input"))
    )
    (net (code "86") (name "Net-(U4-G)") (class "Default")
      (node (ref "R55") (pin "2") (pinfunction "2_2") (pintype "passive"))
      (node (ref "SW28") (pin "1") (pinfunction "1_1") (pintype "passive"))
      (node (ref "U4") (pin "5") (pinfunction "G_5") (pintype "input"))
    )
    (net (code "87") (name "Net-(U4-H)") (class "Default")
      (node (ref "R53") (pin "2") (pinfunction "2_2") (pintype "passive"))
      (node (ref "SW27") (pin "1") (pinfunction "1_1") (pintype "passive"))
      (node (ref "U4") (pin "6") (pinfunction "H_6") (pintype "input"))
    )
    (net (code "88") (name "Net-(U5A-BOOT0)") (class "Default")
      (node (ref "R70") (pin "2") (pinfunction "2_2") (pintype "passive"))
      (node (ref "U5") (pin "44") (pinfunction "BOOT0_44") (pintype "input"))
    )
    (net (code "89") (name "Net-(U5A-NRST)") (class "Default")
      (node (ref "C8") (pin "2") (pinfunction "2_2") (pintype "passive"))
      (node (ref "R76") (pin "2") (pinfunction "2_2") (pintype "passive"))
      (node (ref "SW35") (pin "1") (pinfunction "1_1") (pintype "passive"))
      (node (ref "U5") (pin "7") (pinfunction "NRST_7") (pintype "bidirectional"))
    )
    (net (code "90") (name "Net-(U5A-PB2)") (class "Default")
      (node (ref "R75") (pin "2") (pinfunction "2_2") (pintype "passive"))
      (node (ref "U5") (pin "20") (pinfunction "PB2_20") (pintype "bidirectional"))
    )
    (net (code "91") (name "Net-(U5A-PD0-OSC_IN)") (class "Default")
      (node (ref "C7") (pin "1") (pinfunction "1_1") (pintype "passive"))
      (node (ref "U5") (pin "5") (pinfunction "PD0-OSC_IN_5") (pintype "bidirectional"))
      (node (ref "X1") (pin "2") (pinfunction "X2_2") (pintype "passive"))
    )
    (net (code "92") (name "Net-(U5A-PD1-OSC_OUT)") (class "Default")
      (node (ref "C9") (pin "1") (pinfunction "1_1") (pintype "passive"))
      (node (ref "U5") (pin "6") (pinfunction "PD1-OSC_OUT_6") (pintype "bidirectional"))
      (node (ref "X1") (pin "1") (pinfunction "X1_1") (pintype "passive"))
    )
    (net (code "93") (name "unconnected-(P4-SHLD1-Pad5)") (class "Default")
      (node (ref "P4") (pin "5") (pinfunction "SHLD1_5") (pintype "passive"))
    )
    (net (code "94") (name "unconnected-(P4-SHLD2-Pad6)") (class "Default")
      (node (ref "P4") (pin "6") (pinfunction "SHLD2_6") (pintype "passive"))
    )
    (net (code "95") (name "unconnected-(SW1-34-Pad3)") (class "Default")
      (node (ref "SW1") (pin "3") (pinfunction "34_3") (pintype "passive"))
    )
    (net (code "96") (name "unconnected-(SW1-Pad2)") (class "Default")
      (node (ref "SW1") (pin "2") (pinfunction "2_2") (pintype "passive"))
    )
    (net (code "97") (name "unconnected-(SW2-34-Pad3)") (class "Default")
      (node (ref "SW2") (pin "3") (pinfunction "34_3") (pintype "passive"))
    )
    (net (code "98") (name "unconnected-(SW2-Pad2)") (class "Default")
      (node (ref "SW2") (pin "2") (pinfunction "2_2") (pintype "passive"))
    )
    (net (code "99") (name "unconnected-(SW3-34-Pad3)") (class "Default")
      (node (ref "SW3") (pin "3") (pinfunction "34_3") (pintype "passive"))
    )
    (net (code "100") (name "unconnected-(SW3-Pad2)") (class "Default")
      (node (ref "SW3") (pin "2") (pinfunction "2_2") (pintype "passive"))
    )
    (net (code "101") (name "unconnected-(SW4-34-Pad3)") (class "Default")
      (node (ref "SW4") (pin "3") (pinfunction "34_3") (pintype "passive"))
    )
    (net (code "102") (name "unconnected-(SW4-Pad2)") (class "Default")
      (node (ref "SW4") (pin "2") (pinfunction "2_2") (pintype "passive"))
    )
    (net (code "103") (name "unconnected-(SW5-34-Pad3)") (class "Default")
      (node (ref "SW5") (pin "3") (pinfunction "34_3") (pintype "passive"))
    )
    (net (code "104") (name "unconnected-(SW5-Pad2)") (class "Default")
      (node (ref "SW5") (pin "2") (pinfunction "2_2") (pintype "passive"))
    )
    (net (code "105") (name "unconnected-(SW6-34-Pad3)") (class "Default")
      (node (ref "SW6") (pin "3") (pinfunction "34_3") (pintype "passive"))
    )
    (net (code "106") (name "unconnected-(SW6-Pad2)") (class "Default")
      (node (ref "SW6") (pin "2") (pinfunction "2_2") (pintype "passive"))
    )
    (net (code "107") (name "unconnected-(SW7-34-Pad3)") (class "Default")
      (node (ref "SW7") (pin "3") (pinfunction "34_3") (pintype "passive"))
    )
    (net (code "108") (name "unconnected-(SW7-Pad2)") (class "Default")
      (node (ref "SW7") (pin "2") (pinfunction "2_2") (pintype "passive"))
    )
    (net (code "109") (name "unconnected-(SW8-34-Pad3)") (class "Default")
      (node (ref "SW8") (pin "3") (pinfunction "34_3") (pintype "passive"))
    )
    (net (code "110") (name "unconnected-(SW8-Pad2)") (class "Default")
      (node (ref "SW8") (pin "2") (pinfunction "2_2") (pintype "passive"))
    )
    (net (code "111") (name "unconnected-(SW9-34-Pad3)") (class "Default")
      (node (ref "SW9") (pin "3") (pinfunction "34_3") (pintype "passive"))
    )
    (net (code "112") (name "unconnected-(SW9-Pad2)") (class "Default")
      (node (ref "SW9") (pin "2") (pinfunction "2_2") (pintype "passive"))
    )
    (net (code "113") (name "unconnected-(SW10-34-Pad3)") (class "Default")
      (node (ref "SW10") (pin "3") (pinfunction "34_3") (pintype "passive"))
    )
    (net (code "114") (name "unconnected-(SW10-Pad2)") (class "Default")
      (node (ref "SW10") (pin "2") (pinfunction "2_2") (pintype "passive"))
    )
    (net (code "115") (name "unconnected-(SW11-34-Pad3)") (class "Default")
      (node (ref "SW11") (pin "3") (pinfunction "34_3") (pintype "passive"))
    )
    (net (code "116") (name "unconnected-(SW11-Pad2)") (class "Default")
      (node (ref "SW11") (pin "2") (pinfunction "2_2") (pintype "passive"))
    )
    (net (code "117") (name "unconnected-(SW12-34-Pad3)") (class "Default")
      (node (ref "SW12") (pin "3") (pinfunction "34_3") (pintype "passive"))
    )
    (net (code "118") (name "unconnected-(SW12-Pad2)") (class "Default")
      (node (ref "SW12") (pin "2") (pinfunction "2_2") (pintype "passive"))
    )
    (net (code "119") (name "unconnected-(SW13-34-Pad3)") (class "Default")
      (node (ref "SW13") (pin "3") (pinfunction "34_3") (pintype "passive"))
    )
    (net (code "120") (name "unconnected-(SW13-Pad2)") (class "Default")
      (node (ref "SW13") (pin "2") (pinfunction "2_2") (pintype "passive"))
    )
    (net (code "121") (name "unconnected-(SW14-34-Pad3)") (class "Default")
      (node (ref "SW14") (pin "3") (pinfunction "34_3") (pintype "passive"))
    )
    (net (code "122") (name "unconnected-(SW14-Pad2)") (class "Default")
      (node (ref "SW14") (pin "2") (pinfunction "2_2") (pintype "passive"))
    )
    (net (code "123") (name "unconnected-(SW15-34-Pad3)") (class "Default")
      (node (ref "SW15") (pin "3") (pinfunction "34_3") (pintype "passive"))
    )
    (net (code "124") (name "unconnected-(SW15-Pad2)") (class "Default")
      (node (ref "SW15") (pin "2") (pinfunction "2_2") (pintype "passive"))
    )
    (net (code "125") (name "unconnected-(SW16-34-Pad3)") (class "Default")
      (node (ref "SW16") (pin "3") (pinfunction "34_3") (pintype "passive"))
    )
    (net (code "126") (name "unconnected-(SW16-Pad2)") (class "Default")
      (node (ref "SW16") (pin "2") (pinfunction "2_2") (pintype "passive"))
    )
    (net (code "127") (name "unconnected-(SW17-34-Pad3)") (class "Default")
      (node (ref "SW17") (pin "3") (pinfunction "34_3") (pintype "passive"))
    )
    (net (code "128") (name "unconnected-(SW17-Pad2)") (class "Default")
      (node (ref "SW17") (pin "2") (pinfunction "2_2") (pintype "passive"))
    )
    (net (code "129") (name "unconnected-(SW18-34-Pad3)") (class "Default")
      (node (ref "SW18") (pin "3") (pinfunction "34_3") (pintype "passive"))
    )
    (net (code "130") (name "unconnected-(SW18-Pad2)") (class "Default")
      (node (ref "SW18") (pin "2") (pinfunction "2_2") (pintype "passive"))
    )
    (net (code "131") (name "unconnected-(SW19-34-Pad3)") (class "Default")
      (node (ref "SW19") (pin "3") (pinfunction "34_3") (pintype "passive"))
    )
    (net (code "132") (name "unconnected-(SW19-Pad2)") (class "Default")
      (node (ref "SW19") (pin "2") (pinfunction "2_2") (pintype "passive"))
    )
    (net (code "133") (name "unconnected-(SW20-34-Pad3)") (class "Default")
      (node (ref "SW20") (pin "3") (pinfunction "34_3") (pintype "passive"))
    )
    (net (code "134") (name "unconnected-(SW20-Pad2)") (class "Default")
      (node (ref "SW20") (pin "2") (pinfunction "2_2") (pintype "passive"))
    )
    (net (code "135") (name "unconnected-(SW21-34-Pad3)") (class "Default")
      (node (ref "SW21") (pin "3") (pinfunction "34_3") (pintype "passive"))
    )
    (net (code "136") (name "unconnected-(SW21-Pad2)") (class "Default")
      (node (ref "SW21") (pin "2") (pinfunction "2_2") (pintype "passive"))
    )
    (net (code "137") (name "unconnected-(SW22-34-Pad3)") (class "Default")
      (node (ref "SW22") (pin "3") (pinfunction "34_3") (pintype "passive"))
    )
    (net (code "138") (name "unconnected-(SW22-Pad2)") (class "Default")
      (node (ref "SW22") (pin "2") (pinfunction "2_2") (pintype "passive"))
    )
    (net (code "139") (name "unconnected-(SW23-34-Pad3)") (class "Default")
      (node (ref "SW23") (pin "3") (pinfunction "34_3") (pintype "passive"))
    )
    (net (code "140") (name "unconnected-(SW23-Pad2)") (class "Default")
      (node (ref "SW23") (pin "2") (pinfunction "2_2") (pintype "passive"))
    )
    (net (code "141") (name "unconnected-(SW24-34-Pad3)") (class "Default")
      (node (ref "SW24") (pin "3") (pinfunction "34_3") (pintype "passive"))
    )
    (net (code "142") (name "unconnected-(SW24-Pad2)") (class "Default")
      (node (ref "SW24") (pin "2") (pinfunction "2_2") (pintype "passive"))
    )
    (net (code "143") (name "unconnected-(SW25-34-Pad3)") (class "Default")
      (node (ref "SW25") (pin "3") (pinfunction "34_3") (pintype "passive"))
    )
    (net (code "144") (name "unconnected-(SW25-Pad2)") (class "Default")
      (node (ref "SW25") (pin "2") (pinfunction "2_2") (pintype "passive"))
    )
    (net (code "145") (name "unconnected-(SW26-34-Pad3)") (class "Default")
      (node (ref "SW26") (pin "3") (pinfunction "34_3") (pintype "passive"))
    )
    (net (code "146") (name "unconnected-(SW26-Pad2)") (class "Default")
      (node (ref "SW26") (pin "2") (pinfunction "2_2") (pintype "passive"))
    )
    (net (code "147") (name "unconnected-(SW27-34-Pad3)") (class "Default")
      (node (ref "SW27") (pin "3") (pinfunction "34_3") (pintype "passive"))
    )
    (net (code "148") (name "unconnected-(SW27-Pad2)") (class "Default")
      (node (ref "SW27") (pin "2") (pinfunction "2_2") (pintype "passive"))
    )
    (net (code "149") (name "unconnected-(SW28-34-Pad3)") (class "Default")
      (node (ref "SW28") (pin "3") (pinfunction "34_3") (pintype "passive"))
    )
    (net (code "150") (name "unconnected-(SW28-Pad2)") (class "Default")
      (node (ref "SW28") (pin "2") (pinfunction "2_2") (pintype "passive"))
    )
    (net (code "151") (name "unconnected-(SW29-34-Pad3)") (class "Default")
      (node (ref "SW29") (pin "3") (pinfunction "34_3") (pintype "passive"))
    )
    (net (code "152") (name "unconnected-(SW29-Pad2)") (class "Default")
      (node (ref "SW29") (pin "2") (pinfunction "2_2") (pintype "passive"))
    )
    (net (code "153") (name "unconnected-(SW30-34-Pad3)") (class "Default")
      (node (ref "SW30") (pin "3") (pinfunction "34_3") (pintype "passive"))
    )
    (net (code "154") (name "unconnected-(SW30-Pad2)") (class "Default")
      (node (ref "SW30") (pin "2") (pinfunction "2_2") (pintype "passive"))
    )
    (net (code "155") (name "unconnected-(SW31-34-Pad3)") (class "Default")
      (node (ref "SW31") (pin "3") (pinfunction "34_3") (pintype "passive"))
    )
    (net (code "156") (name "unconnected-(SW31-Pad2)") (class "Default")
      (node (ref "SW31") (pin "2") (pinfunction "2_2") (pintype "passive"))
    )
    (net (code "157") (name "unconnected-(SW32-34-Pad3)") (class "Default")
      (node (ref "SW32") (pin "3") (pinfunction "34_3") (pintype "passive"))
    )
    (net (code "158") (name "unconnected-(SW32-Pad2)") (class "Default")
      (node (ref "SW32") (pin "2") (pinfunction "2_2") (pintype "passive"))
    )
    (net (code "159") (name "unconnected-(SW33-34-Pad3)") (class "Default")
      (node (ref "SW33") (pin "3") (pinfunction "34_3") (pintype "passive"))
    )
    (net (code "160") (name "unconnected-(SW33-Pad2)") (class "Default")
      (node (ref "SW33") (pin "2") (pinfunction "2_2") (pintype "passive"))
    )
    (net (code "161") (name "unconnected-(SW34-34-Pad3)") (class "Default")
      (node (ref "SW34") (pin "3") (pinfunction "34_3") (pintype "passive"))
    )
    (net (code "162") (name "unconnected-(SW34-Pad2)") (class "Default")
      (node (ref "SW34") (pin "2") (pinfunction "2_2") (pintype "passive"))
    )
    (net (code "163") (name "unconnected-(U1-~{Q}H-Pad7)") (class "Default")
      (node (ref "U1") (pin "7") (pinfunction "~{Q}H_7") (pintype "output"))
    )
    (net (code "164") (name "unconnected-(U2-~{Q}H-Pad7)") (class "Default")
      (node (ref "U2") (pin "7") (pinfunction "~{Q}H_7") (pintype "output"))
    )
    (net (code "165") (name "unconnected-(U3-~{Q}H-Pad7)") (class "Default")
      (node (ref "U3") (pin "7") (pinfunction "~{Q}H_7") (pintype "output"))
    )
    (net (code "166") (name "unconnected-(U4-~{Q}H-Pad7)") (class "Default")
      (node (ref "U4") (pin "7") (pinfunction "~{Q}H_7") (pintype "output"))
    )
    (net (code "167") (name "unconnected-(U5A-PA0-WKUP-Pad10)") (class "Default")
      (node (ref "U5") (pin "10") (pinfunction "PA0-WKUP_10") (pintype "bidirectional"))
    )
    (net (code "168") (name "unconnected-(U5A-PA1-Pad11)") (class "Default")
      (node (ref "U5") (pin "11") (pinfunction "PA1_11") (pintype "bidirectional"))
    )
    (net (code "169") (name "unconnected-(U5A-PA2-Pad12)") (class "Default")
      (node (ref "U5") (pin "12") (pinfunction "PA2_12") (pintype "bidirectional"))
    )
    (net (code "170") (name "unconnected-(U5A-PA3-Pad13)") (class "Default")
      (node (ref "U5") (pin "13") (pinfunction "PA3_13") (pintype "bidirectional"))
    )
    (net (code "171") (name "unconnected-(U5A-PA4-Pad14)") (class "Default")
      (node (ref "U5") (pin "14") (pinfunction "PA4_14") (pintype "bidirectional"))
    )
    (net (code "172") (name "unconnected-(U5A-PA5-Pad15)") (class "Default")
      (node (ref "U5") (pin "15") (pinfunction "PA5_15") (pintype "bidirectional"))
    )
    (net (code "173") (name "unconnected-(U5A-PA6-Pad16)") (class "Default")
      (node (ref "U5") (pin "16") (pinfunction "PA6_16") (pintype "bidirectional"))
    )
    (net (code "174") (name "unconnected-(U5A-PA7-Pad17)") (class "Default")
      (node (ref "U5") (pin "17") (pinfunction "PA7_17") (pintype "bidirectional"))
    )
    (net (code "175") (name "unconnected-(U5A-PA8-Pad29)") (class "Default")
      (node (ref "U5") (pin "29") (pinfunction "PA8_29") (pintype "bidirectional"))
    )
    (net (code "176") (name "unconnected-(U5A-PA15-Pad38)") (class "Default")
      (node (ref "U5") (pin "38") (pinfunction "PA15_38") (pintype "bidirectional"))
    )
    (net (code "177") (name "unconnected-(U5A-PB0-Pad18)") (class "Default")
      (node (ref "U5") (pin "18") (pinfunction "PB0_18") (pintype "bidirectional"))
    )
    (net (code "178") (name "unconnected-(U5A-PB1-Pad19)") (class "Default")
      (node (ref "U5") (pin "19") (pinfunction "PB1_19") (pintype "bidirectional"))
    )
    (net (code "179") (name "unconnected-(U5A-PB4-Pad40)") (class "Default")
      (node (ref "U5") (pin "40") (pinfunction "PB4_40") (pintype "bidirectional"))
    )
    (net (code "180") (name "unconnected-(U5A-PB5-Pad41)") (class "Default")
      (node (ref "U5") (pin "41") (pinfunction "PB5_41") (pintype "bidirectional"))
    )
    (net (code "181") (name "unconnected-(U5A-PB6-Pad42)") (class "Default")
      (node (ref "U5") (pin "42") (pinfunction "PB6_42") (pintype "bidirectional"))
    )
    (net (code "182") (name "unconnected-(U5A-PB7-Pad43)") (class "Default")
      (node (ref "U5") (pin "43") (pinfunction "PB7_43") (pintype "bidirectional"))
    )
    (net (code "183") (name "unconnected-(U5A-PB8-Pad45)") (class "Default")
      (node (ref "U5") (pin "45") (pinfunction "PB8_45") (pintype "bidirectional"))
    )
    (net (code "184") (name "unconnected-(U5A-PB13-Pad26)") (class "Default")
      (node (ref "U5") (pin "26") (pinfunction "PB13_26") (pintype "bidirectional"))
    )
    (net (code "185") (name "unconnected-(U5A-PB14-Pad27)") (class "Default")
      (node (ref "U5") (pin "27") (pinfunction "PB14_27") (pintype "bidirectional"))
    )
    (net (code "186") (name "unconnected-(U5A-PB15-Pad28)") (class "Default")
      (node (ref "U5") (pin "28") (pinfunction "PB15_28") (pintype "bidirectional"))
    )
    (net (code "187") (name "unconnected-(U5A-PC13-TAMPER-RTC-Pad2)") (class "Default")
      (node (ref "U5") (pin "2") (pinfunction "PC13-TAMPER-RTC_2") (pintype "bidirectional"))
    )
    (net (code "188") (name "unconnected-(U5A-PC14-OSC32_IN-Pad3)") (class "Default")
      (node (ref "U5") (pin "3") (pinfunction "PC14-OSC32_IN_3") (pintype "bidirectional"))
    )
    (net (code "189") (name "unconnected-(U5A-PC15-OSC32_OUT-Pad4)") (class "Default")
      (node (ref "U5") (pin "4") (pinfunction "PC15-OSC32_OUT_4") (pintype "bidirectional"))
    )
    (net (code "190") (name "unconnected-(U5B-VBAT-Pad1)") (class "Default")
      (node (ref "U5") (pin "1") (pinfunction "VBAT_1") (pintype "power_in"))
    )
  )
)
